# MMU8L.net
KiCad netlist of a schematic drawn in EAGLE
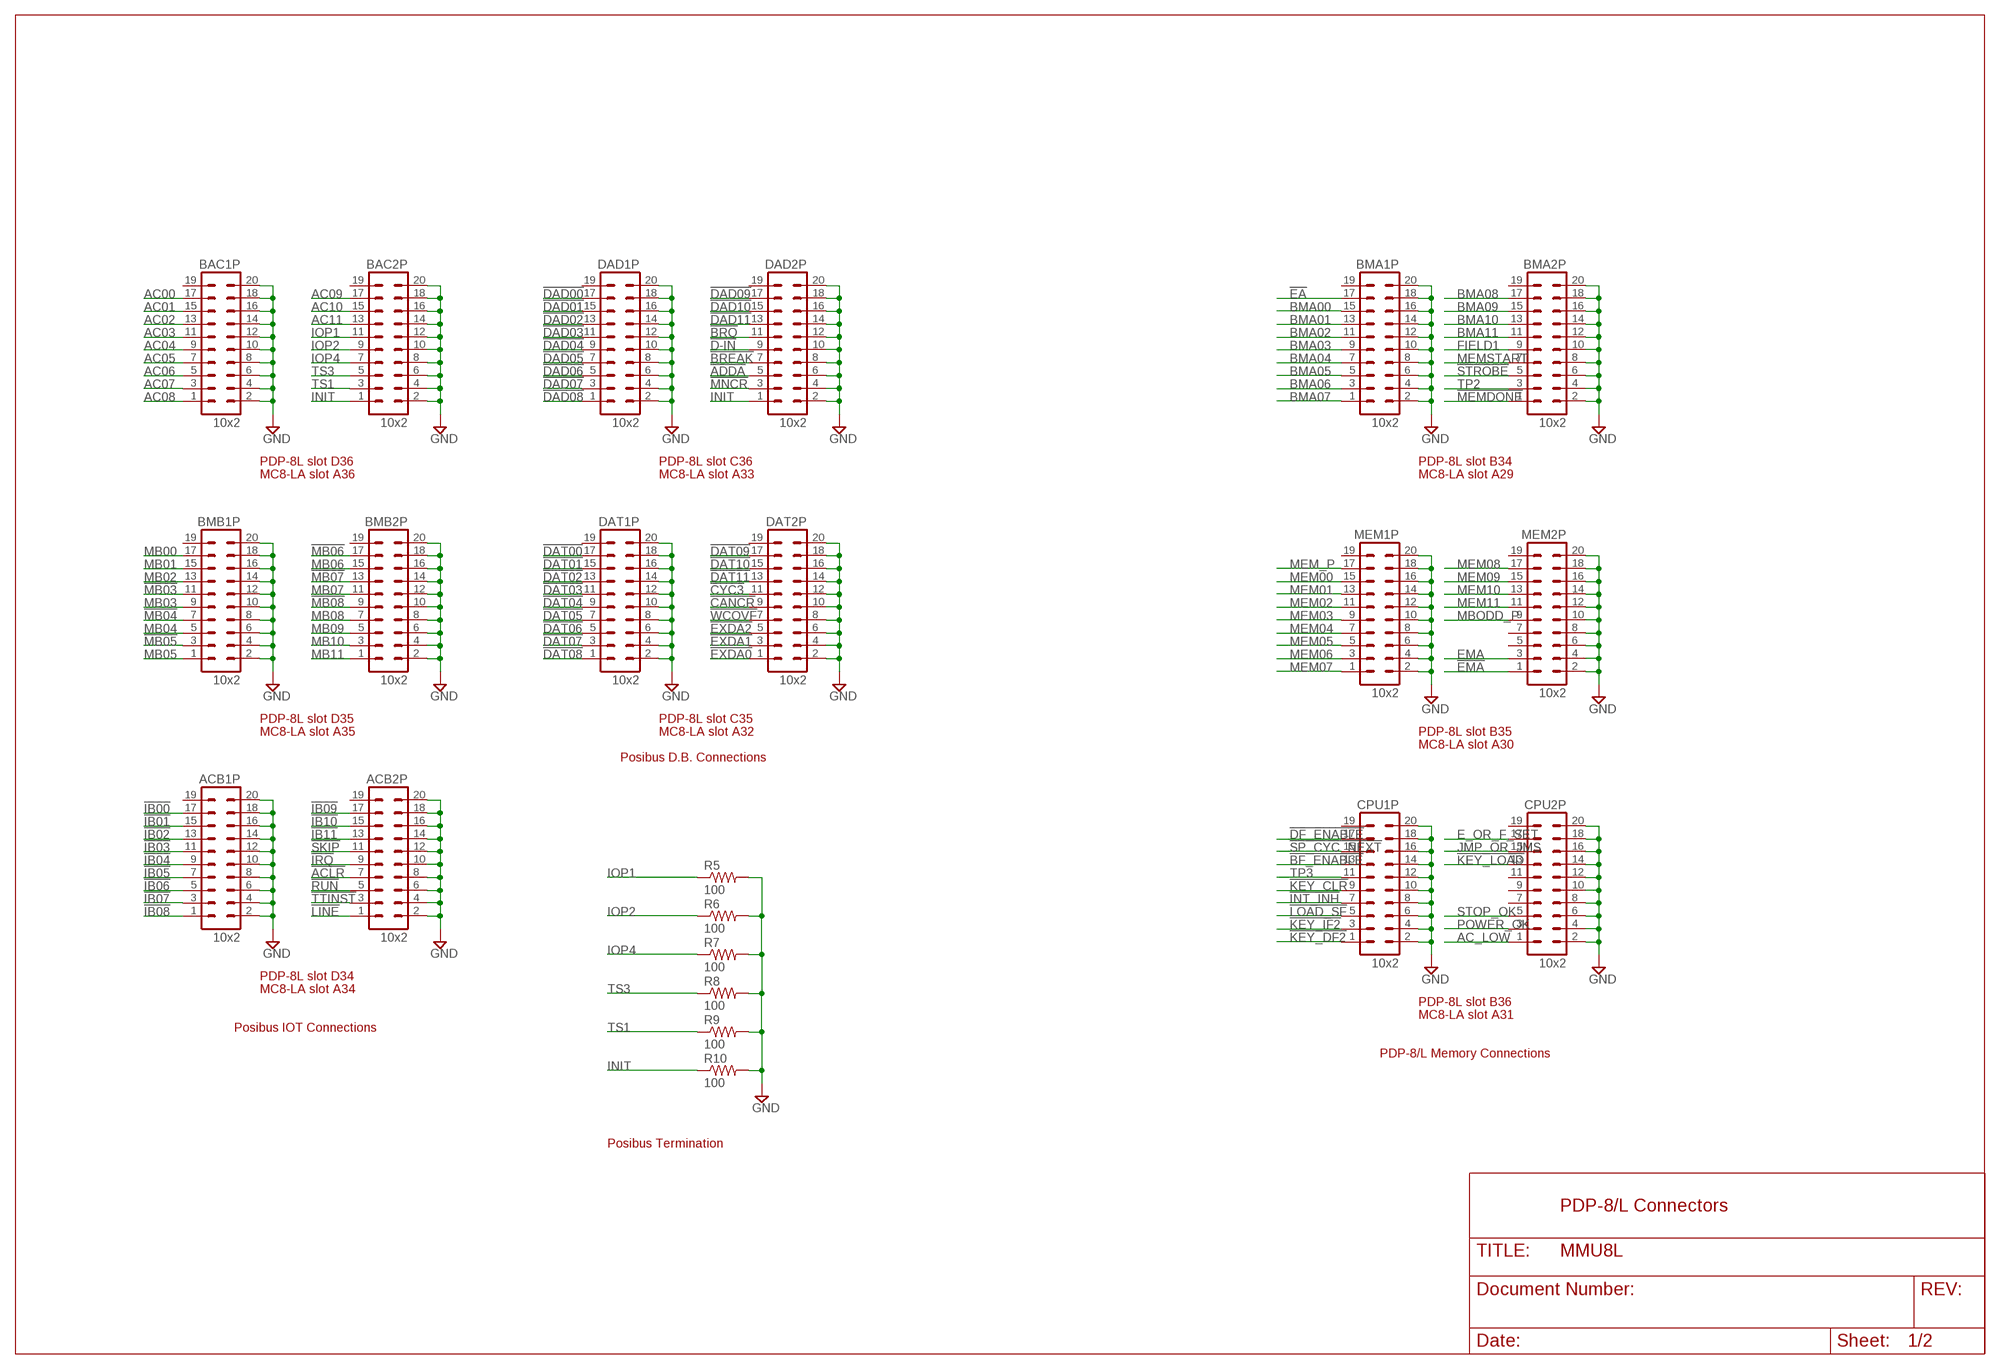
[diagram p0: schematic, sheet 1]
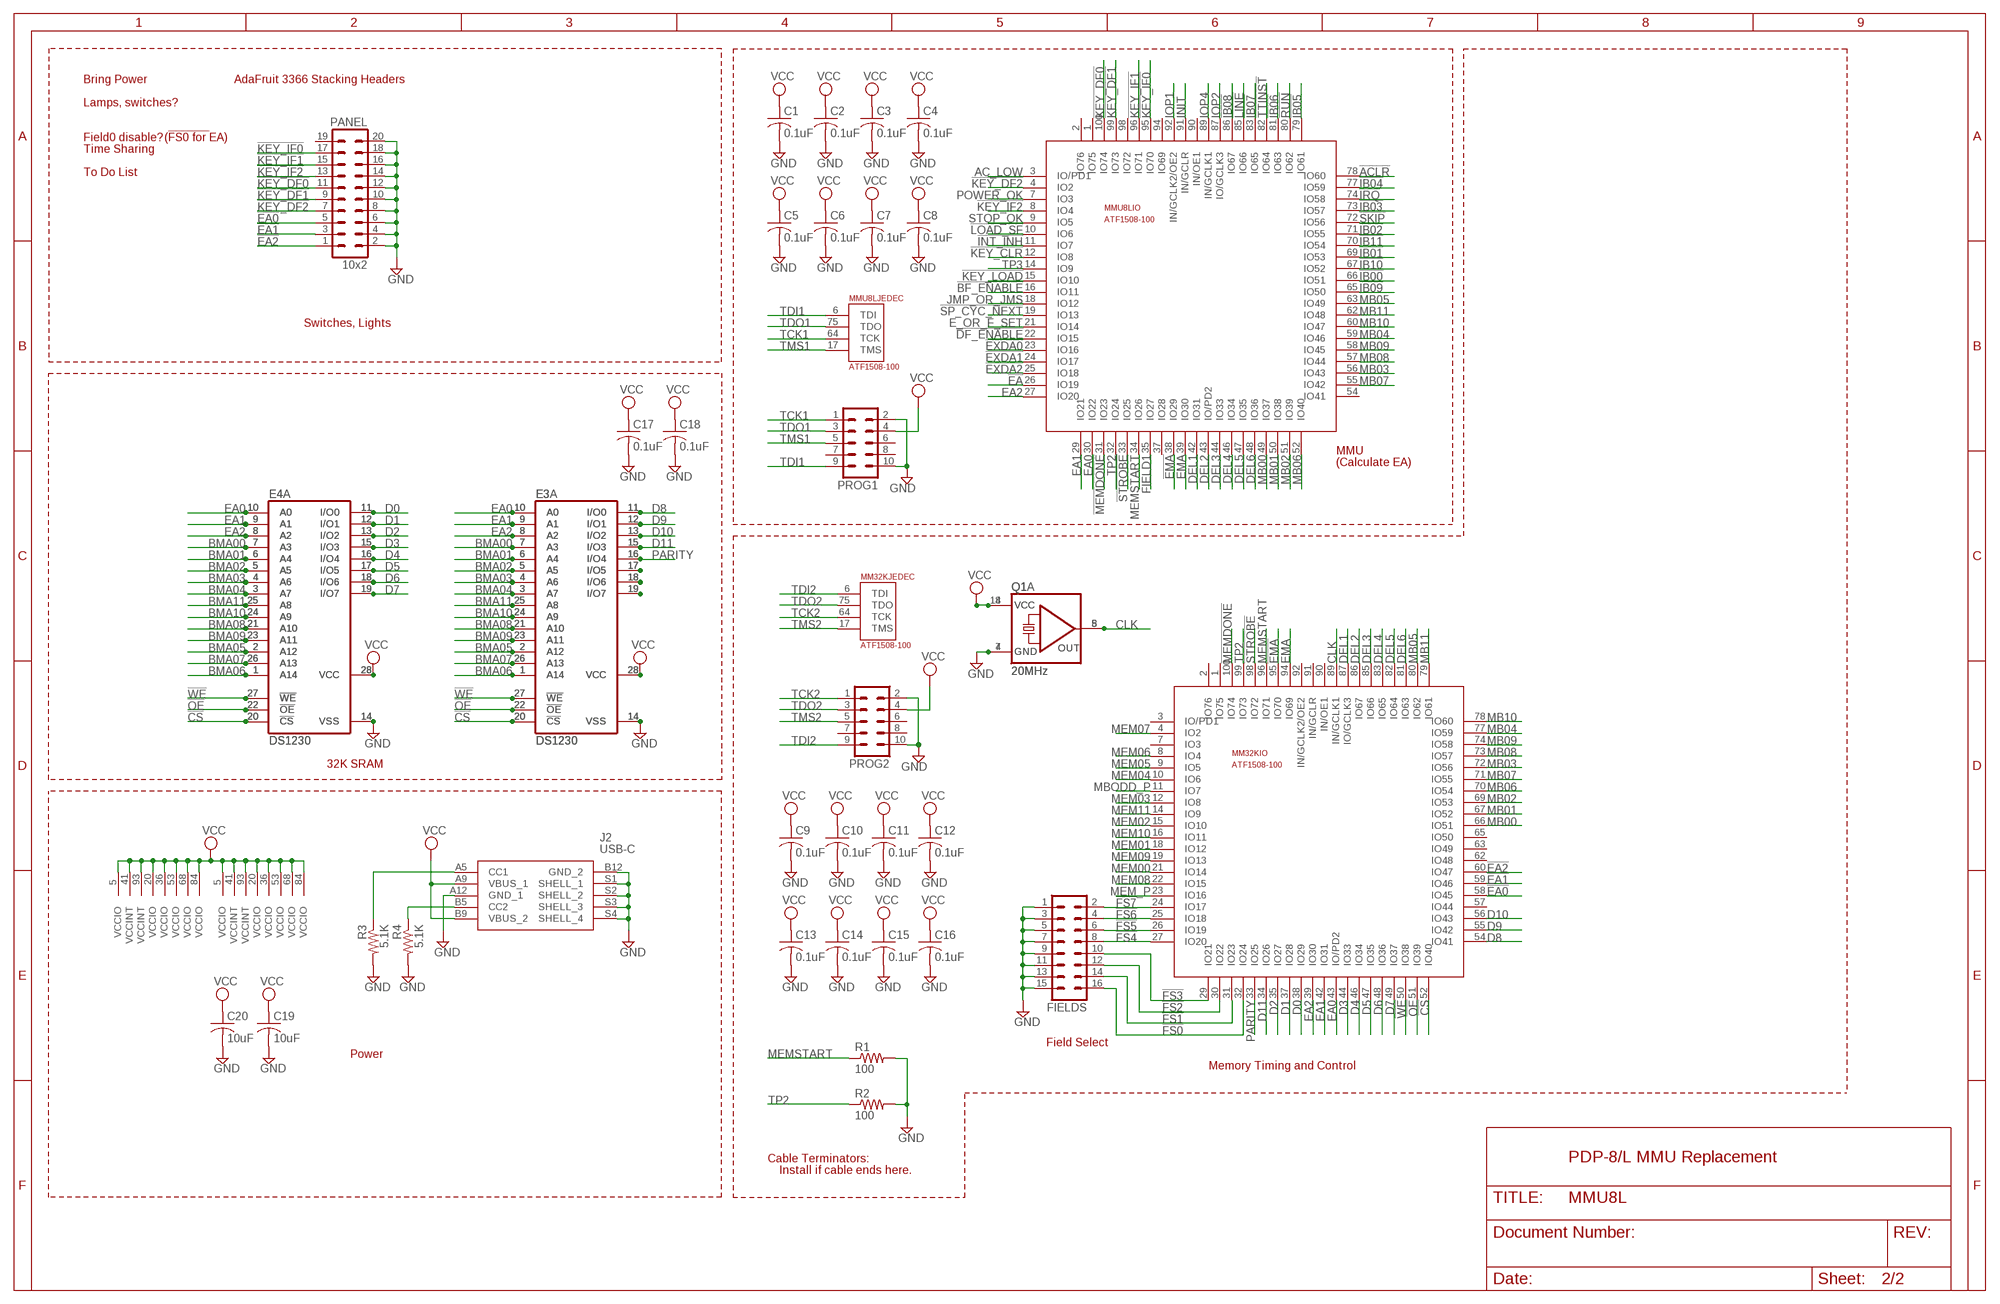
[diagram p1: schematic, sheet 2]

(export (version "E")
  (design (tool "Eeschema 10.0.6"))
  (components
    (comp (ref "C1")
      (value "0.1uF")
      (footprint "eagle-import:C0805")
      (libsource (lib "eagle-import") (part "C-USC0805"))
    )
    (comp (ref "C2")
      (value "0.1uF")
      (footprint "eagle-import:C0805")
      (libsource (lib "eagle-import") (part "C-USC0805"))
    )
    (comp (ref "C3")
      (value "0.1uF")
      (footprint "eagle-import:C0805")
      (libsource (lib "eagle-import") (part "C-USC0805"))
    )
    (comp (ref "C4")
      (value "0.1uF")
      (footprint "eagle-import:C0805")
      (libsource (lib "eagle-import") (part "C-USC0805"))
    )
    (comp (ref "C5")
      (value "0.1uF")
      (footprint "eagle-import:C0805")
      (libsource (lib "eagle-import") (part "C-USC0805"))
    )
    (comp (ref "C6")
      (value "0.1uF")
      (footprint "eagle-import:C0805")
      (libsource (lib "eagle-import") (part "C-USC0805"))
    )
    (comp (ref "C7")
      (value "0.1uF")
      (footprint "eagle-import:C0805")
      (libsource (lib "eagle-import") (part "C-USC0805"))
    )
    (comp (ref "C8")
      (value "0.1uF")
      (footprint "eagle-import:C0805")
      (libsource (lib "eagle-import") (part "C-USC0805"))
    )
    (comp (ref "C9")
      (value "0.1uF")
      (footprint "eagle-import:C0805")
      (libsource (lib "eagle-import") (part "C-USC0805"))
    )
    (comp (ref "C10")
      (value "0.1uF")
      (footprint "eagle-import:C0805")
      (libsource (lib "eagle-import") (part "C-USC0805"))
    )
    (comp (ref "C11")
      (value "0.1uF")
      (footprint "eagle-import:C0805")
      (libsource (lib "eagle-import") (part "C-USC0805"))
    )
    (comp (ref "C12")
      (value "0.1uF")
      (footprint "eagle-import:C0805")
      (libsource (lib "eagle-import") (part "C-USC0805"))
    )
    (comp (ref "C13")
      (value "0.1uF")
      (footprint "eagle-import:C0805")
      (libsource (lib "eagle-import") (part "C-USC0805"))
    )
    (comp (ref "C14")
      (value "0.1uF")
      (footprint "eagle-import:C0805")
      (libsource (lib "eagle-import") (part "C-USC0805"))
    )
    (comp (ref "C15")
      (value "0.1uF")
      (footprint "eagle-import:C0805")
      (libsource (lib "eagle-import") (part "C-USC0805"))
    )
    (comp (ref "C16")
      (value "0.1uF")
      (footprint "eagle-import:C0805")
      (libsource (lib "eagle-import") (part "C-USC0805"))
    )
    (comp (ref "C17")
      (value "0.1uF")
      (footprint "eagle-import:C0805")
      (libsource (lib "eagle-import") (part "C-USC0805"))
    )
    (comp (ref "C18")
      (value "0.1uF")
      (footprint "eagle-import:C0805")
      (libsource (lib "eagle-import") (part "C-USC0805"))
    )
    (comp (ref "C19")
      (value "10uF")
      (footprint "eagle-import:C0805")
      (libsource (lib "eagle-import") (part "C-USC0805"))
    )
    (comp (ref "C20")
      (value "10uF")
      (footprint "eagle-import:C0805")
      (libsource (lib "eagle-import") (part "C-USC0805"))
    )
    (comp (ref "E3")
      (value "DS1230")
      (footprint "eagle-import:DIL28-6")
      (libsource (lib "eagle-import") (part "62256P"))
    )
    (comp (ref "E3A")
      (value "DS1230")
      (footprint "eagle-import:DIL28-3")
      (libsource (lib "eagle-import") (part "62832P"))
    )
    (comp (ref "E4")
      (value "DS1230")
      (footprint "eagle-import:DIL28-6")
      (libsource (lib "eagle-import") (part "62256P"))
    )
    (comp (ref "E4A")
      (value "DS1230")
      (footprint "eagle-import:DIL28-3")
      (libsource (lib "eagle-import") (part "62832P"))
    )
    (comp (ref "FIELDS")
      (value "MA08-2")
      (footprint "eagle-import:MA08-2")
      (libsource (lib "eagle-import") (part "MA08-2"))
    )
    (comp (ref "J2")
      (value "USB-C")
      (footprint "eagle-import:USB497000A")
      (fields (field (name "MANUFACTURER_PART_NUMBER") "USB4970-00-A"))
      (libsource (lib "eagle-import") (part "USB4970-00-A"))
    )
    (comp (ref "MM32K")
      (value "ATF1508-100")
      (footprint "eagle-import:PQFP-100")
      (libsource (lib "eagle-import") (part "ATF150X100PQFP"))
    )
    (comp (ref "MMU8L")
      (value "ATF1508-100")
      (footprint "eagle-import:PQFP-100")
      (libsource (lib "eagle-import") (part "ATF150X100PQFP"))
    )
    (comp (ref "PANEL")
      (value "10x2")
      (footprint "eagle-import:MA10-2")
      (libsource (lib "eagle-import") (part "MA10-2"))
    )
    (comp (ref "PROG1")
      (value "ML10")
      (footprint "eagle-import:ML10")
      (libsource (lib "eagle-import") (part "ML10"))
    )
    (comp (ref "PROG2")
      (value "ML10")
      (footprint "eagle-import:ML10")
      (libsource (lib "eagle-import") (part "ML10"))
    )
    (comp (ref "Q1")
      (value "20MHz")
      (footprint "eagle-import:DIL14S")
      (libsource (lib "eagle-import") (part "QG5860"))
    )
    (comp (ref "Q1A")
      (value "20MHz")
      (footprint "eagle-import:DIL08S")
      (libsource (lib "eagle-import") (part "QG5460"))
    )
    (comp (ref "R1")
      (value "100")
      (footprint "eagle-import:R1206")
      (libsource (lib "eagle-import") (part "R-US_R1206"))
    )
    (comp (ref "R2")
      (value "100")
      (footprint "eagle-import:R1206")
      (libsource (lib "eagle-import") (part "R-US_R1206"))
    )
    (comp (ref "R3")
      (value "5.1K")
      (footprint "eagle-import:R0805")
      (libsource (lib "eagle-import") (part "R-US_R0805"))
    )
    (comp (ref "R4")
      (value "5.1K")
      (footprint "eagle-import:R0805")
      (libsource (lib "eagle-import") (part "R-US_R0805"))
    )
    (comp (ref "ACB1P")
      (value "10x2")
      (footprint "eagle-import:MA10-2")
      (libsource (lib "eagle-import") (part "MA10-2"))
    )
    (comp (ref "ACB2P")
      (value "10x2")
      (footprint "eagle-import:MA10-2")
      (libsource (lib "eagle-import") (part "MA10-2"))
    )
    (comp (ref "BAC1P")
      (value "10x2")
      (footprint "eagle-import:MA10-2")
      (libsource (lib "eagle-import") (part "MA10-2"))
    )
    (comp (ref "BAC2P")
      (value "10x2")
      (footprint "eagle-import:MA10-2")
      (libsource (lib "eagle-import") (part "MA10-2"))
    )
    (comp (ref "BMA1P")
      (value "10x2")
      (footprint "eagle-import:MA10-2")
      (libsource (lib "eagle-import") (part "MA10-2"))
    )
    (comp (ref "BMA2P")
      (value "10x2")
      (footprint "eagle-import:MA10-2")
      (libsource (lib "eagle-import") (part "MA10-2"))
    )
    (comp (ref "BMB1P")
      (value "10x2")
      (footprint "eagle-import:MA10-2")
      (libsource (lib "eagle-import") (part "MA10-2"))
    )
    (comp (ref "BMB2P")
      (value "10x2")
      (footprint "eagle-import:MA10-2")
      (libsource (lib "eagle-import") (part "MA10-2"))
    )
    (comp (ref "CPU1P")
      (value "10x2")
      (footprint "eagle-import:MA10-2")
      (libsource (lib "eagle-import") (part "MA10-2"))
    )
    (comp (ref "CPU2P")
      (value "10x2")
      (footprint "eagle-import:MA10-2")
      (libsource (lib "eagle-import") (part "MA10-2"))
    )
    (comp (ref "DAD1P")
      (value "10x2")
      (footprint "eagle-import:MA10-2")
      (libsource (lib "eagle-import") (part "MA10-2"))
    )
    (comp (ref "DAD2P")
      (value "10x2")
      (footprint "eagle-import:MA10-2")
      (libsource (lib "eagle-import") (part "MA10-2"))
    )
    (comp (ref "DAT1P")
      (value "10x2")
      (footprint "eagle-import:MA10-2")
      (libsource (lib "eagle-import") (part "MA10-2"))
    )
    (comp (ref "DAT2P")
      (value "10x2")
      (footprint "eagle-import:MA10-2")
      (libsource (lib "eagle-import") (part "MA10-2"))
    )
    (comp (ref "MEM1P")
      (value "10x2")
      (footprint "eagle-import:MA10-2")
      (libsource (lib "eagle-import") (part "MA10-2"))
    )
    (comp (ref "MEM2P")
      (value "10x2")
      (footprint "eagle-import:MA10-2")
      (libsource (lib "eagle-import") (part "MA10-2"))
    )
    (comp (ref "R5")
      (value "100")
      (footprint "eagle-import:R1206")
      (libsource (lib "eagle-import") (part "R-US_R1206"))
    )
    (comp (ref "R6")
      (value "100")
      (footprint "eagle-import:R1206")
      (libsource (lib "eagle-import") (part "R-US_R1206"))
    )
    (comp (ref "R7")
      (value "100")
      (footprint "eagle-import:R1206")
      (libsource (lib "eagle-import") (part "R-US_R1206"))
    )
    (comp (ref "R8")
      (value "100")
      (footprint "eagle-import:R1206")
      (libsource (lib "eagle-import") (part "R-US_R1206"))
    )
    (comp (ref "R9")
      (value "100")
      (footprint "eagle-import:R1206")
      (libsource (lib "eagle-import") (part "R-US_R1206"))
    )
    (comp (ref "R10")
      (value "100")
      (footprint "eagle-import:R1206")
      (libsource (lib "eagle-import") (part "R-US_R1206"))
    )
  )
  (nets
    (net (code "1") (name "AC00") (class "Default")
      (node (ref "BAC1P") (pin "17") (pinfunction "17_17") (pintype "passive"))
    )
    (net (code "2") (name "AC01") (class "Default")
      (node (ref "BAC1P") (pin "15") (pinfunction "15_15") (pintype "passive"))
    )
    (net (code "3") (name "AC02") (class "Default")
      (node (ref "BAC1P") (pin "13") (pinfunction "13_13") (pintype "passive"))
    )
    (net (code "4") (name "AC03") (class "Default")
      (node (ref "BAC1P") (pin "11") (pinfunction "11_11") (pintype "passive"))
    )
    (net (code "5") (name "AC04") (class "Default")
      (node (ref "BAC1P") (pin "9") (pinfunction "9_9") (pintype "passive"))
    )
    (net (code "6") (name "AC05") (class "Default")
      (node (ref "BAC1P") (pin "7") (pinfunction "7_7") (pintype "passive"))
    )
    (net (code "7") (name "AC06") (class "Default")
      (node (ref "BAC1P") (pin "5") (pinfunction "5_5") (pintype "passive"))
    )
    (net (code "8") (name "AC07") (class "Default")
      (node (ref "BAC1P") (pin "3") (pinfunction "3_3") (pintype "passive"))
    )
    (net (code "9") (name "AC08") (class "Default")
      (node (ref "BAC1P") (pin "1") (pinfunction "1_1") (pintype "passive"))
    )
    (net (code "10") (name "AC09") (class "Default")
      (node (ref "BAC2P") (pin "17") (pinfunction "17_17") (pintype "passive"))
    )
    (net (code "11") (name "AC10") (class "Default")
      (node (ref "BAC2P") (pin "15") (pinfunction "15_15") (pintype "passive"))
    )
    (net (code "12") (name "AC11") (class "Default")
      (node (ref "BAC2P") (pin "13") (pinfunction "13_13") (pintype "passive"))
    )
    (net (code "13") (name "AC_LOW") (class "Default")
      (node (ref "CPU2P") (pin "1") (pinfunction "1_1") (pintype "passive"))
      (node (ref "MMU8L") (pin "3") (pinfunction "IO/PD1_3") (pintype "bidirectional"))
    )
    (net (code "14") (name "BMA00") (class "Default")
      (node (ref "BMA1P") (pin "15") (pinfunction "15_15") (pintype "passive"))
      (node (ref "E3") (pin "7") (pinfunction "A3_7") (pintype "input"))
      (node (ref "E3A") (pin "7") (pinfunction "A3_7") (pintype "input"))
      (node (ref "E4") (pin "7") (pinfunction "A3_7") (pintype "input"))
      (node (ref "E4A") (pin "7") (pinfunction "A3_7") (pintype "input"))
    )
    (net (code "15") (name "BMA01") (class "Default")
      (node (ref "BMA1P") (pin "13") (pinfunction "13_13") (pintype "passive"))
      (node (ref "E3") (pin "6") (pinfunction "A4_6") (pintype "input"))
      (node (ref "E3A") (pin "6") (pinfunction "A4_6") (pintype "input"))
      (node (ref "E4") (pin "6") (pinfunction "A4_6") (pintype "input"))
      (node (ref "E4A") (pin "6") (pinfunction "A4_6") (pintype "input"))
    )
    (net (code "16") (name "BMA02") (class "Default")
      (node (ref "BMA1P") (pin "11") (pinfunction "11_11") (pintype "passive"))
      (node (ref "E3") (pin "5") (pinfunction "A5_5") (pintype "input"))
      (node (ref "E3A") (pin "5") (pinfunction "A5_5") (pintype "input"))
      (node (ref "E4") (pin "5") (pinfunction "A5_5") (pintype "input"))
      (node (ref "E4A") (pin "5") (pinfunction "A5_5") (pintype "input"))
    )
    (net (code "17") (name "BMA03") (class "Default")
      (node (ref "BMA1P") (pin "9") (pinfunction "9_9") (pintype "passive"))
      (node (ref "E3") (pin "4") (pinfunction "A6_4") (pintype "input"))
      (node (ref "E3A") (pin "4") (pinfunction "A6_4") (pintype "input"))
      (node (ref "E4") (pin "4") (pinfunction "A6_4") (pintype "input"))
      (node (ref "E4A") (pin "4") (pinfunction "A6_4") (pintype "input"))
    )
    (net (code "18") (name "BMA04") (class "Default")
      (node (ref "BMA1P") (pin "7") (pinfunction "7_7") (pintype "passive"))
      (node (ref "E3") (pin "3") (pinfunction "A7_3") (pintype "input"))
      (node (ref "E3A") (pin "3") (pinfunction "A7_3") (pintype "input"))
      (node (ref "E4") (pin "3") (pinfunction "A7_3") (pintype "input"))
      (node (ref "E4A") (pin "3") (pinfunction "A7_3") (pintype "input"))
    )
    (net (code "19") (name "BMA05") (class "Default")
      (node (ref "BMA1P") (pin "5") (pinfunction "5_5") (pintype "passive"))
      (node (ref "E3") (pin "2") (pinfunction "A12_2") (pintype "input"))
      (node (ref "E3A") (pin "2") (pinfunction "A12_2") (pintype "input"))
      (node (ref "E4") (pin "2") (pinfunction "A12_2") (pintype "input"))
      (node (ref "E4A") (pin "2") (pinfunction "A12_2") (pintype "input"))
    )
    (net (code "20") (name "BMA06") (class "Default")
      (node (ref "BMA1P") (pin "3") (pinfunction "3_3") (pintype "passive"))
      (node (ref "E3") (pin "1") (pinfunction "A14_1") (pintype "input"))
      (node (ref "E3A") (pin "1") (pinfunction "A14_1") (pintype "input"))
      (node (ref "E4") (pin "1") (pinfunction "A14_1") (pintype "input"))
      (node (ref "E4A") (pin "1") (pinfunction "A14_1") (pintype "input"))
    )
    (net (code "21") (name "BMA07") (class "Default")
      (node (ref "BMA1P") (pin "1") (pinfunction "1_1") (pintype "passive"))
      (node (ref "E3") (pin "26") (pinfunction "A13_26") (pintype "input"))
      (node (ref "E3A") (pin "26") (pinfunction "A13_26") (pintype "input"))
      (node (ref "E4") (pin "26") (pinfunction "A13_26") (pintype "input"))
      (node (ref "E4A") (pin "26") (pinfunction "A13_26") (pintype "input"))
    )
    (net (code "22") (name "BMA08") (class "Default")
      (node (ref "BMA2P") (pin "17") (pinfunction "17_17") (pintype "passive"))
      (node (ref "E3") (pin "21") (pinfunction "A10_21") (pintype "input"))
      (node (ref "E3A") (pin "21") (pinfunction "A10_21") (pintype "input"))
      (node (ref "E4") (pin "21") (pinfunction "A10_21") (pintype "input"))
      (node (ref "E4A") (pin "21") (pinfunction "A10_21") (pintype "input"))
    )
    (net (code "23") (name "BMA09") (class "Default")
      (node (ref "BMA2P") (pin "15") (pinfunction "15_15") (pintype "passive"))
      (node (ref "E3") (pin "23") (pinfunction "A11_23") (pintype "input"))
      (node (ref "E3A") (pin "23") (pinfunction "A11_23") (pintype "input"))
      (node (ref "E4") (pin "23") (pinfunction "A11_23") (pintype "input"))
      (node (ref "E4A") (pin "23") (pinfunction "A11_23") (pintype "input"))
    )
    (net (code "24") (name "BMA10") (class "Default")
      (node (ref "BMA2P") (pin "13") (pinfunction "13_13") (pintype "passive"))
      (node (ref "E3") (pin "24") (pinfunction "A9_24") (pintype "input"))
      (node (ref "E3A") (pin "24") (pinfunction "A9_24") (pintype "input"))
      (node (ref "E4") (pin "24") (pinfunction "A9_24") (pintype "input"))
      (node (ref "E4A") (pin "24") (pinfunction "A9_24") (pintype "input"))
    )
    (net (code "25") (name "BMA11") (class "Default")
      (node (ref "BMA2P") (pin "11") (pinfunction "11_11") (pintype "passive"))
      (node (ref "E3") (pin "25") (pinfunction "A8_25") (pintype "input"))
      (node (ref "E3A") (pin "25") (pinfunction "A8_25") (pintype "input"))
      (node (ref "E4") (pin "25") (pinfunction "A8_25") (pintype "input"))
      (node (ref "E4A") (pin "25") (pinfunction "A8_25") (pintype "input"))
    )
    (net (code "26") (name "CLK") (class "Default")
      (node (ref "MM32K") (pin "89") (pinfunction "IN/GCLK1_89") (pintype "input"))
      (node (ref "Q1") (pin "8") (pinfunction "OUT_8") (pintype "output"))
      (node (ref "Q1A") (pin "5") (pinfunction "OUT_5") (pintype "output"))
    )
    (net (code "27") (name "D0") (class "Default")
      (node (ref "E4") (pin "11") (pinfunction "I/O0_11") (pintype "bidirectional"))
      (node (ref "E4A") (pin "11") (pinfunction "I/O0_11") (pintype "bidirectional"))
      (node (ref "MM32K") (pin "38") (pinfunction "IO29_38") (pintype "bidirectional"))
    )
    (net (code "28") (name "D1") (class "Default")
      (node (ref "E4") (pin "12") (pinfunction "I/O1_12") (pintype "bidirectional"))
      (node (ref "E4A") (pin "12") (pinfunction "I/O1_12") (pintype "bidirectional"))
      (node (ref "MM32K") (pin "37") (pinfunction "IO28_37") (pintype "bidirectional"))
    )
    (net (code "29") (name "D2") (class "Default")
      (node (ref "E4") (pin "13") (pinfunction "I/O2_13") (pintype "bidirectional"))
      (node (ref "E4A") (pin "13") (pinfunction "I/O2_13") (pintype "bidirectional"))
      (node (ref "MM32K") (pin "35") (pinfunction "IO27_35") (pintype "bidirectional"))
    )
    (net (code "30") (name "D3") (class "Default")
      (node (ref "E4") (pin "15") (pinfunction "I/O3_15") (pintype "bidirectional"))
      (node (ref "E4A") (pin "15") (pinfunction "I/O3_15") (pintype "bidirectional"))
      (node (ref "MM32K") (pin "44") (pinfunction "IO33_44") (pintype "bidirectional"))
    )
    (net (code "31") (name "D4") (class "Default")
      (node (ref "E4") (pin "16") (pinfunction "I/O4_16") (pintype "bidirectional"))
      (node (ref "E4A") (pin "16") (pinfunction "I/O4_16") (pintype "bidirectional"))
      (node (ref "MM32K") (pin "46") (pinfunction "IO34_46") (pintype "bidirectional"))
    )
    (net (code "32") (name "D5") (class "Default")
      (node (ref "E4") (pin "17") (pinfunction "I/O5_17") (pintype "bidirectional"))
      (node (ref "E4A") (pin "17") (pinfunction "I/O5_17") (pintype "bidirectional"))
      (node (ref "MM32K") (pin "47") (pinfunction "IO35_47") (pintype "bidirectional"))
    )
    (net (code "33") (name "D6") (class "Default")
      (node (ref "E4") (pin "18") (pinfunction "I/O6_18") (pintype "bidirectional"))
      (node (ref "E4A") (pin "18") (pinfunction "I/O6_18") (pintype "bidirectional"))
      (node (ref "MM32K") (pin "48") (pinfunction "IO36_48") (pintype "bidirectional"))
    )
    (net (code "34") (name "D7") (class "Default")
      (node (ref "E4") (pin "19") (pinfunction "I/O7_19") (pintype "bidirectional"))
      (node (ref "E4A") (pin "19") (pinfunction "I/O7_19") (pintype "bidirectional"))
      (node (ref "MM32K") (pin "49") (pinfunction "IO37_49") (pintype "bidirectional"))
    )
    (net (code "35") (name "D8") (class "Default")
      (node (ref "E3") (pin "11") (pinfunction "I/O0_11") (pintype "bidirectional"))
      (node (ref "E3A") (pin "11") (pinfunction "I/O0_11") (pintype "bidirectional"))
      (node (ref "MM32K") (pin "54") (pinfunction "IO41_54") (pintype "bidirectional"))
    )
    (net (code "36") (name "D9") (class "Default")
      (node (ref "E3") (pin "12") (pinfunction "I/O1_12") (pintype "bidirectional"))
      (node (ref "E3A") (pin "12") (pinfunction "I/O1_12") (pintype "bidirectional"))
      (node (ref "MM32K") (pin "55") (pinfunction "IO42_55") (pintype "bidirectional"))
    )
    (net (code "37") (name "D10") (class "Default")
      (node (ref "E3") (pin "13") (pinfunction "I/O2_13") (pintype "bidirectional"))
      (node (ref "E3A") (pin "13") (pinfunction "I/O2_13") (pintype "bidirectional"))
      (node (ref "MM32K") (pin "56") (pinfunction "IO43_56") (pintype "bidirectional"))
    )
    (net (code "38") (name "D11") (class "Default")
      (node (ref "E3") (pin "15") (pinfunction "I/O3_15") (pintype "bidirectional"))
      (node (ref "E3A") (pin "15") (pinfunction "I/O3_15") (pintype "bidirectional"))
      (node (ref "MM32K") (pin "34") (pinfunction "IO26_34") (pintype "bidirectional"))
    )
    (net (code "39") (name "DEL1") (class "Default")
      (node (ref "MM32K") (pin "87") (pinfunction "IO/GCLK3_87") (pintype "bidirectional"))
      (node (ref "MMU8L") (pin "42") (pinfunction "IO31_42") (pintype "bidirectional"))
    )
    (net (code "40") (name "DEL2") (class "Default")
      (node (ref "MM32K") (pin "86") (pinfunction "IO67_86") (pintype "bidirectional"))
      (node (ref "MMU8L") (pin "43") (pinfunction "IO/PD2_43") (pintype "bidirectional"))
    )
    (net (code "41") (name "DEL3") (class "Default")
      (node (ref "MM32K") (pin "85") (pinfunction "IO66_85") (pintype "bidirectional"))
      (node (ref "MMU8L") (pin "44") (pinfunction "IO33_44") (pintype "bidirectional"))
    )
    (net (code "42") (name "DEL4") (class "Default")
      (node (ref "MM32K") (pin "83") (pinfunction "IO65_83") (pintype "bidirectional"))
      (node (ref "MMU8L") (pin "46") (pinfunction "IO34_46") (pintype "bidirectional"))
    )
    (net (code "43") (name "DEL5") (class "Default")
      (node (ref "MM32K") (pin "82") (pinfunction "IO64_82") (pintype "bidirectional"))
      (node (ref "MMU8L") (pin "47") (pinfunction "IO35_47") (pintype "bidirectional"))
    )
    (net (code "44") (name "DEL6") (class "Default")
      (node (ref "MM32K") (pin "81") (pinfunction "IO63_81") (pintype "bidirectional"))
      (node (ref "MMU8L") (pin "48") (pinfunction "IO36_48") (pintype "bidirectional"))
    )
    (net (code "45") (name "EA0") (class "Default")
      (node (ref "E3") (pin "10") (pinfunction "A0_10") (pintype "input"))
      (node (ref "E3A") (pin "10") (pinfunction "A0_10") (pintype "input"))
      (node (ref "E4") (pin "10") (pinfunction "A0_10") (pintype "input"))
      (node (ref "E4A") (pin "10") (pinfunction "A0_10") (pintype "input"))
      (node (ref "MM32K") (pin "43") (pinfunction "IO/PD2_43") (pintype "bidirectional"))
      (node (ref "MMU8L") (pin "30") (pinfunction "IO22_30") (pintype "bidirectional"))
    )
    (net (code "46") (name "EA1") (class "Default")
      (node (ref "E3") (pin "9") (pinfunction "A1_9") (pintype "input"))
      (node (ref "E3A") (pin "9") (pinfunction "A1_9") (pintype "input"))
      (node (ref "E4") (pin "9") (pinfunction "A1_9") (pintype "input"))
      (node (ref "E4A") (pin "9") (pinfunction "A1_9") (pintype "input"))
      (node (ref "MM32K") (pin "42") (pinfunction "IO31_42") (pintype "bidirectional"))
      (node (ref "MMU8L") (pin "29") (pinfunction "IO21_29") (pintype "bidirectional"))
    )
    (net (code "47") (name "EA2") (class "Default")
      (node (ref "E3") (pin "8") (pinfunction "A2_8") (pintype "input"))
      (node (ref "E3A") (pin "8") (pinfunction "A2_8") (pintype "input"))
      (node (ref "E4") (pin "8") (pinfunction "A2_8") (pintype "input"))
      (node (ref "E4A") (pin "8") (pinfunction "A2_8") (pintype "input"))
      (node (ref "MM32K") (pin "39") (pinfunction "IO30_39") (pintype "bidirectional"))
      (node (ref "MMU8L") (pin "27") (pinfunction "IO20_27") (pintype "bidirectional"))
    )
    (net (code "48") (name "EMA") (class "Default")
      (node (ref "MEM2P") (pin "3") (pinfunction "3_3") (pintype "passive"))
      (node (ref "MM32K") (pin "94") (pinfunction "IO69_94") (pintype "bidirectional"))
      (node (ref "MMU8L") (pin "39") (pinfunction "IO30_39") (pintype "bidirectional"))
    )
    (net (code "49") (name "E_OR_F_SET") (class "Default")
      (node (ref "CPU2P") (pin "17") (pinfunction "17_17") (pintype "passive"))
      (node (ref "MMU8L") (pin "21") (pinfunction "IO14_21") (pintype "bidirectional"))
    )
    (net (code "50") (name "FIELD1") (class "Default")
      (node (ref "BMA2P") (pin "9") (pinfunction "9_9") (pintype "passive"))
      (node (ref "MMU8L") (pin "35") (pinfunction "IO27_35") (pintype "bidirectional"))
    )
    (net (code "51") (name "GND") (class "Default")
      (node (ref "ACB1P") (pin "10") (pinfunction "10_10") (pintype "passive"))
      (node (ref "ACB1P") (pin "12") (pinfunction "12_12") (pintype "passive"))
      (node (ref "ACB1P") (pin "14") (pinfunction "14_14") (pintype "passive"))
      (node (ref "ACB1P") (pin "16") (pinfunction "16_16") (pintype "passive"))
      (node (ref "ACB1P") (pin "18") (pinfunction "18_18") (pintype "passive"))
      (node (ref "ACB1P") (pin "2") (pinfunction "2_2") (pintype "passive"))
      (node (ref "ACB1P") (pin "20") (pinfunction "20_20") (pintype "passive"))
      (node (ref "ACB1P") (pin "4") (pinfunction "4_4") (pintype "passive"))
      (node (ref "ACB1P") (pin "6") (pinfunction "6_6") (pintype "passive"))
      (node (ref "ACB1P") (pin "8") (pinfunction "8_8") (pintype "passive"))
      (node (ref "ACB2P") (pin "10") (pinfunction "10_10") (pintype "passive"))
      (node (ref "ACB2P") (pin "12") (pinfunction "12_12") (pintype "passive"))
      (node (ref "ACB2P") (pin "14") (pinfunction "14_14") (pintype "passive"))
      (node (ref "ACB2P") (pin "16") (pinfunction "16_16") (pintype "passive"))
      (node (ref "ACB2P") (pin "18") (pinfunction "18_18") (pintype "passive"))
      (node (ref "ACB2P") (pin "2") (pinfunction "2_2") (pintype "passive"))
      (node (ref "ACB2P") (pin "20") (pinfunction "20_20") (pintype "passive"))
      (node (ref "ACB2P") (pin "4") (pinfunction "4_4") (pintype "passive"))
      (node (ref "ACB2P") (pin "6") (pinfunction "6_6") (pintype "passive"))
      (node (ref "ACB2P") (pin "8") (pinfunction "8_8") (pintype "passive"))
      (node (ref "BAC1P") (pin "10") (pinfunction "10_10") (pintype "passive"))
      (node (ref "BAC1P") (pin "12") (pinfunction "12_12") (pintype "passive"))
      (node (ref "BAC1P") (pin "14") (pinfunction "14_14") (pintype "passive"))
      (node (ref "BAC1P") (pin "16") (pinfunction "16_16") (pintype "passive"))
      (node (ref "BAC1P") (pin "18") (pinfunction "18_18") (pintype "passive"))
      (node (ref "BAC1P") (pin "2") (pinfunction "2_2") (pintype "passive"))
      (node (ref "BAC1P") (pin "20") (pinfunction "20_20") (pintype "passive"))
      (node (ref "BAC1P") (pin "4") (pinfunction "4_4") (pintype "passive"))
      (node (ref "BAC1P") (pin "6") (pinfunction "6_6") (pintype "passive"))
      (node (ref "BAC1P") (pin "8") (pinfunction "8_8") (pintype "passive"))
      (node (ref "BAC2P") (pin "10") (pinfunction "10_10") (pintype "passive"))
      (node (ref "BAC2P") (pin "12") (pinfunction "12_12") (pintype "passive"))
      (node (ref "BAC2P") (pin "14") (pinfunction "14_14") (pintype "passive"))
      (node (ref "BAC2P") (pin "16") (pinfunction "16_16") (pintype "passive"))
      (node (ref "BAC2P") (pin "18") (pinfunction "18_18") (pintype "passive"))
      (node (ref "BAC2P") (pin "2") (pinfunction "2_2") (pintype "passive"))
      (node (ref "BAC2P") (pin "20") (pinfunction "20_20") (pintype "passive"))
      (node (ref "BAC2P") (pin "4") (pinfunction "4_4") (pintype "passive"))
      (node (ref "BAC2P") (pin "6") (pinfunction "6_6") (pintype "passive"))
      (node (ref "BAC2P") (pin "8") (pinfunction "8_8") (pintype "passive"))
      (node (ref "BMA1P") (pin "10") (pinfunction "10_10") (pintype "passive"))
      (node (ref "BMA1P") (pin "12") (pinfunction "12_12") (pintype "passive"))
      (node (ref "BMA1P") (pin "14") (pinfunction "14_14") (pintype "passive"))
      (node (ref "BMA1P") (pin "16") (pinfunction "16_16") (pintype "passive"))
      (node (ref "BMA1P") (pin "18") (pinfunction "18_18") (pintype "passive"))
      (node (ref "BMA1P") (pin "2") (pinfunction "2_2") (pintype "passive"))
      (node (ref "BMA1P") (pin "20") (pinfunction "20_20") (pintype "passive"))
      (node (ref "BMA1P") (pin "4") (pinfunction "4_4") (pintype "passive"))
      (node (ref "BMA1P") (pin "6") (pinfunction "6_6") (pintype "passive"))
      (node (ref "BMA1P") (pin "8") (pinfunction "8_8") (pintype "passive"))
      (node (ref "BMA2P") (pin "10") (pinfunction "10_10") (pintype "passive"))
      (node (ref "BMA2P") (pin "12") (pinfunction "12_12") (pintype "passive"))
      (node (ref "BMA2P") (pin "14") (pinfunction "14_14") (pintype "passive"))
      (node (ref "BMA2P") (pin "16") (pinfunction "16_16") (pintype "passive"))
      (node (ref "BMA2P") (pin "18") (pinfunction "18_18") (pintype "passive"))
      (node (ref "BMA2P") (pin "2") (pinfunction "2_2") (pintype "passive"))
      (node (ref "BMA2P") (pin "20") (pinfunction "20_20") (pintype "passive"))
      (node (ref "BMA2P") (pin "4") (pinfunction "4_4") (pintype "passive"))
      (node (ref "BMA2P") (pin "6") (pinfunction "6_6") (pintype "passive"))
      (node (ref "BMA2P") (pin "8") (pinfunction "8_8") (pintype "passive"))
      (node (ref "BMB1P") (pin "10") (pinfunction "10_10") (pintype "passive"))
      (node (ref "BMB1P") (pin "12") (pinfunction "12_12") (pintype "passive"))
      (node (ref "BMB1P") (pin "14") (pinfunction "14_14") (pintype "passive"))
      (node (ref "BMB1P") (pin "16") (pinfunction "16_16") (pintype "passive"))
      (node (ref "BMB1P") (pin "18") (pinfunction "18_18") (pintype "passive"))
      (node (ref "BMB1P") (pin "2") (pinfunction "2_2") (pintype "passive"))
      (node (ref "BMB1P") (pin "20") (pinfunction "20_20") (pintype "passive"))
      (node (ref "BMB1P") (pin "4") (pinfunction "4_4") (pintype "passive"))
      (node (ref "BMB1P") (pin "6") (pinfunction "6_6") (pintype "passive"))
      (node (ref "BMB1P") (pin "8") (pinfunction "8_8") (pintype "passive"))
      (node (ref "BMB2P") (pin "10") (pinfunction "10_10") (pintype "passive"))
      (node (ref "BMB2P") (pin "12") (pinfunction "12_12") (pintype "passive"))
      (node (ref "BMB2P") (pin "14") (pinfunction "14_14") (pintype "passive"))
      (node (ref "BMB2P") (pin "16") (pinfunction "16_16") (pintype "passive"))
      (node (ref "BMB2P") (pin "18") (pinfunction "18_18") (pintype "passive"))
      (node (ref "BMB2P") (pin "2") (pinfunction "2_2") (pintype "passive"))
      (node (ref "BMB2P") (pin "20") (pinfunction "20_20") (pintype "passive"))
      (node (ref "BMB2P") (pin "4") (pinfunction "4_4") (pintype "passive"))
      (node (ref "BMB2P") (pin "6") (pinfunction "6_6") (pintype "passive"))
      (node (ref "BMB2P") (pin "8") (pinfunction "8_8") (pintype "passive"))
      (node (ref "C1") (pin "2") (pinfunction "2_2") (pintype "passive"))
      (node (ref "C10") (pin "2") (pinfunction "2_2") (pintype "passive"))
      (node (ref "C11") (pin "2") (pinfunction "2_2") (pintype "passive"))
      (node (ref "C12") (pin "2") (pinfunction "2_2") (pintype "passive"))
      (node (ref "C13") (pin "2") (pinfunction "2_2") (pintype "passive"))
      (node (ref "C14") (pin "2") (pinfunction "2_2") (pintype "passive"))
      (node (ref "C15") (pin "2") (pinfunction "2_2") (pintype "passive"))
      (node (ref "C16") (pin "2") (pinfunction "2_2") (pintype "passive"))
      (node (ref "C17") (pin "2") (pinfunction "2_2") (pintype "passive"))
      (node (ref "C18") (pin "2") (pinfunction "2_2") (pintype "passive"))
      (node (ref "C19") (pin "2") (pinfunction "2_2") (pintype "passive"))
      (node (ref "C2") (pin "2") (pinfunction "2_2") (pintype "passive"))
      (node (ref "C20") (pin "2") (pinfunction "2_2") (pintype "passive"))
      (node (ref "C3") (pin "2") (pinfunction "2_2") (pintype "passive"))
      (node (ref "C4") (pin "2") (pinfunction "2_2") (pintype "passive"))
      (node (ref "C5") (pin "2") (pinfunction "2_2") (pintype "passive"))
      (node (ref "C6") (pin "2") (pinfunction "2_2") (pintype "passive"))
      (node (ref "C7") (pin "2") (pinfunction "2_2") (pintype "passive"))
      (node (ref "C8") (pin "2") (pinfunction "2_2") (pintype "passive"))
      (node (ref "C9") (pin "2") (pinfunction "2_2") (pintype "passive"))
      (node (ref "CPU1P") (pin "10") (pinfunction "10_10") (pintype "passive"))
      (node (ref "CPU1P") (pin "12") (pinfunction "12_12") (pintype "passive"))
      (node (ref "CPU1P") (pin "14") (pinfunction "14_14") (pintype "passive"))
      (node (ref "CPU1P") (pin "16") (pinfunction "16_16") (pintype "passive"))
      (node (ref "CPU1P") (pin "18") (pinfunction "18_18") (pintype "passive"))
      (node (ref "CPU1P") (pin "2") (pinfunction "2_2") (pintype "passive"))
      (node (ref "CPU1P") (pin "20") (pinfunction "20_20") (pintype "passive"))
      (node (ref "CPU1P") (pin "4") (pinfunction "4_4") (pintype "passive"))
      (node (ref "CPU1P") (pin "6") (pinfunction "6_6") (pintype "passive"))
      (node (ref "CPU1P") (pin "8") (pinfunction "8_8") (pintype "passive"))
      (node (ref "CPU2P") (pin "10") (pinfunction "10_10") (pintype "passive"))
      (node (ref "CPU2P") (pin "12") (pinfunction "12_12") (pintype "passive"))
      (node (ref "CPU2P") (pin "14") (pinfunction "14_14") (pintype "passive"))
      (node (ref "CPU2P") (pin "16") (pinfunction "16_16") (pintype "passive"))
      (node (ref "CPU2P") (pin "18") (pinfunction "18_18") (pintype "passive"))
      (node (ref "CPU2P") (pin "2") (pinfunction "2_2") (pintype "passive"))
      (node (ref "CPU2P") (pin "20") (pinfunction "20_20") (pintype "passive"))
      (node (ref "CPU2P") (pin "4") (pinfunction "4_4") (pintype "passive"))
      (node (ref "CPU2P") (pin "6") (pinfunction "6_6") (pintype "passive"))
      (node (ref "CPU2P") (pin "8") (pinfunction "8_8") (pintype "passive"))
      (node (ref "DAD1P") (pin "10") (pinfunction "10_10") (pintype "passive"))
      (node (ref "DAD1P") (pin "12") (pinfunction "12_12") (pintype "passive"))
      (node (ref "DAD1P") (pin "14") (pinfunction "14_14") (pintype "passive"))
      (node (ref "DAD1P") (pin "16") (pinfunction "16_16") (pintype "passive"))
      (node (ref "DAD1P") (pin "18") (pinfunction "18_18") (pintype "passive"))
      (node (ref "DAD1P") (pin "2") (pinfunction "2_2") (pintype "passive"))
      (node (ref "DAD1P") (pin "20") (pinfunction "20_20") (pintype "passive"))
      (node (ref "DAD1P") (pin "4") (pinfunction "4_4") (pintype "passive"))
      (node (ref "DAD1P") (pin "6") (pinfunction "6_6") (pintype "passive"))
      (node (ref "DAD1P") (pin "8") (pinfunction "8_8") (pintype "passive"))
      (node (ref "DAD2P") (pin "10") (pinfunction "10_10") (pintype "passive"))
      (node (ref "DAD2P") (pin "12") (pinfunction "12_12") (pintype "passive"))
      (node (ref "DAD2P") (pin "14") (pinfunction "14_14") (pintype "passive"))
      (node (ref "DAD2P") (pin "16") (pinfunction "16_16") (pintype "passive"))
      (node (ref "DAD2P") (pin "18") (pinfunction "18_18") (pintype "passive"))
      (node (ref "DAD2P") (pin "2") (pinfunction "2_2") (pintype "passive"))
      (node (ref "DAD2P") (pin "20") (pinfunction "20_20") (pintype "passive"))
      (node (ref "DAD2P") (pin "4") (pinfunction "4_4") (pintype "passive"))
      (node (ref "DAD2P") (pin "6") (pinfunction "6_6") (pintype "passive"))
      (node (ref "DAD2P") (pin "8") (pinfunction "8_8") (pintype "passive"))
      (node (ref "DAT1P") (pin "10") (pinfunction "10_10") (pintype "passive"))
      (node (ref "DAT1P") (pin "12") (pinfunction "12_12") (pintype "passive"))
      (node (ref "DAT1P") (pin "14") (pinfunction "14_14") (pintype "passive"))
      (node (ref "DAT1P") (pin "16") (pinfunction "16_16") (pintype "passive"))
      (node (ref "DAT1P") (pin "18") (pinfunction "18_18") (pintype "passive"))
      (node (ref "DAT1P") (pin "2") (pinfunction "2_2") (pintype "passive"))
      (node (ref "DAT1P") (pin "20") (pinfunction "20_20") (pintype "passive"))
      (node (ref "DAT1P") (pin "4") (pinfunction "4_4") (pintype "passive"))
      (node (ref "DAT1P") (pin "6") (pinfunction "6_6") (pintype "passive"))
      (node (ref "DAT1P") (pin "8") (pinfunction "8_8") (pintype "passive"))
      (node (ref "DAT2P") (pin "10") (pinfunction "10_10") (pintype "passive"))
      (node (ref "DAT2P") (pin "12") (pinfunction "12_12") (pintype "passive"))
      (node (ref "DAT2P") (pin "14") (pinfunction "14_14") (pintype "passive"))
      (node (ref "DAT2P") (pin "16") (pinfunction "16_16") (pintype "passive"))
      (node (ref "DAT2P") (pin "18") (pinfunction "18_18") (pintype "passive"))
      (node (ref "DAT2P") (pin "2") (pinfunction "2_2") (pintype "passive"))
      (node (ref "DAT2P") (pin "20") (pinfunction "20_20") (pintype "passive"))
      (node (ref "DAT2P") (pin "4") (pinfunction "4_4") (pintype "passive"))
      (node (ref "DAT2P") (pin "6") (pinfunction "6_6") (pintype "passive"))
      (node (ref "DAT2P") (pin "8") (pinfunction "8_8") (pintype "passive"))
      (node (ref "E3") (pin "14") (pinfunction "VSS_14") (pintype "power_in"))
      (node (ref "E3A") (pin "14") (pinfunction "VSS_14") (pintype "power_in"))
      (node (ref "E4") (pin "14") (pinfunction "VSS_14") (pintype "power_in"))
      (node (ref "E4A") (pin "14") (pinfunction "VSS_14") (pintype "power_in"))
      (node (ref "FIELDS") (pin "1") (pinfunction "1_1") (pintype "passive"))
      (node (ref "FIELDS") (pin "11") (pinfunction "11_11") (pintype "passive"))
      (node (ref "FIELDS") (pin "13") (pinfunction "13_13") (pintype "passive"))
      (node (ref "FIELDS") (pin "15") (pinfunction "15_15") (pintype "passive"))
      (node (ref "FIELDS") (pin "3") (pinfunction "3_3") (pintype "passive"))
      (node (ref "FIELDS") (pin "5") (pinfunction "5_5") (pintype "passive"))
      (node (ref "FIELDS") (pin "7") (pinfunction "7_7") (pintype "passive"))
      (node (ref "FIELDS") (pin "9") (pinfunction "9_9") (pintype "passive"))
      (node (ref "J2") (pin "A12") (pinfunction "GND_1_A12") (pintype "bidirectional"))
      (node (ref "J2") (pin "B12") (pinfunction "GND_2_B12") (pintype "bidirectional"))
      (node (ref "J2") (pin "S1") (pinfunction "SHELL_1_S1") (pintype "bidirectional"))
      (node (ref "J2") (pin "S2") (pinfunction "SHELL_2_S2") (pintype "bidirectional"))
      (node (ref "J2") (pin "S3") (pinfunction "SHELL_3_S3") (pintype "bidirectional"))
      (node (ref "J2") (pin "S4") (pinfunction "SHELL_4_S4") (pintype "bidirectional"))
      (node (ref "MEM1P") (pin "10") (pinfunction "10_10") (pintype "passive"))
      (node (ref "MEM1P") (pin "12") (pinfunction "12_12") (pintype "passive"))
      (node (ref "MEM1P") (pin "14") (pinfunction "14_14") (pintype "passive"))
      (node (ref "MEM1P") (pin "16") (pinfunction "16_16") (pintype "passive"))
      (node (ref "MEM1P") (pin "18") (pinfunction "18_18") (pintype "passive"))
      (node (ref "MEM1P") (pin "2") (pinfunction "2_2") (pintype "passive"))
      (node (ref "MEM1P") (pin "20") (pinfunction "20_20") (pintype "passive"))
      (node (ref "MEM1P") (pin "4") (pinfunction "4_4") (pintype "passive"))
      (node (ref "MEM1P") (pin "6") (pinfunction "6_6") (pintype "passive"))
      (node (ref "MEM1P") (pin "8") (pinfunction "8_8") (pintype "passive"))
      (node (ref "MEM2P") (pin "10") (pinfunction "10_10") (pintype "passive"))
      (node (ref "MEM2P") (pin "12") (pinfunction "12_12") (pintype "passive"))
      (node (ref "MEM2P") (pin "14") (pinfunction "14_14") (pintype "passive"))
      (node (ref "MEM2P") (pin "16") (pinfunction "16_16") (pintype "passive"))
      (node (ref "MEM2P") (pin "18") (pinfunction "18_18") (pintype "passive"))
      (node (ref "MEM2P") (pin "2") (pinfunction "2_2") (pintype "passive"))
      (node (ref "MEM2P") (pin "20") (pinfunction "20_20") (pintype "passive"))
      (node (ref "MEM2P") (pin "4") (pinfunction "4_4") (pintype "passive"))
      (node (ref "MEM2P") (pin "6") (pinfunction "6_6") (pintype "passive"))
      (node (ref "MEM2P") (pin "8") (pinfunction "8_8") (pintype "passive"))
      (node (ref "PANEL") (pin "10") (pinfunction "10_10") (pintype "passive"))
      (node (ref "PANEL") (pin "12") (pinfunction "12_12") (pintype "passive"))
      (node (ref "PANEL") (pin "14") (pinfunction "14_14") (pintype "passive"))
      (node (ref "PANEL") (pin "16") (pinfunction "16_16") (pintype "passive"))
      (node (ref "PANEL") (pin "18") (pinfunction "18_18") (pintype "passive"))
      (node (ref "PANEL") (pin "2") (pinfunction "2_2") (pintype "passive"))
      (node (ref "PANEL") (pin "20") (pinfunction "20_20") (pintype "passive"))
      (node (ref "PANEL") (pin "4") (pinfunction "4_4") (pintype "passive"))
      (node (ref "PANEL") (pin "6") (pinfunction "6_6") (pintype "passive"))
      (node (ref "PANEL") (pin "8") (pinfunction "8_8") (pintype "passive"))
      (node (ref "PROG1") (pin "10") (pinfunction "10_10") (pintype "passive"))
      (node (ref "PROG1") (pin "2") (pinfunction "2_2") (pintype "passive"))
      (node (ref "PROG2") (pin "10") (pinfunction "10_10") (pintype "passive"))
      (node (ref "PROG2") (pin "2") (pinfunction "2_2") (pintype "passive"))
      (node (ref "Q1") (pin "7") (pinfunction "GND_7") (pintype "power_in"))
      (node (ref "Q1A") (pin "4") (pinfunction "GND_4") (pintype "power_in"))
      (node (ref "R1") (pin "2") (pinfunction "2_2") (pintype "passive"))
      (node (ref "R10") (pin "2") (pinfunction "2_2") (pintype "passive"))
      (node (ref "R2") (pin "2") (pinfunction "2_2") (pintype "passive"))
      (node (ref "R3") (pin "2") (pinfunction "2_2") (pintype "passive"))
      (node (ref "R4") (pin "2") (pinfunction "2_2") (pintype "passive"))
      (node (ref "R5") (pin "2") (pinfunction "2_2") (pintype "passive"))
      (node (ref "R6") (pin "2") (pinfunction "2_2") (pintype "passive"))
      (node (ref "R7") (pin "2") (pinfunction "2_2") (pintype "passive"))
      (node (ref "R8") (pin "2") (pinfunction "2_2") (pintype "passive"))
      (node (ref "R9") (pin "2") (pinfunction "2_2") (pintype "passive"))
    )
    (net (code "52") (name "INIT") (class "Default")
      (node (ref "BAC2P") (pin "1") (pinfunction "1_1") (pintype "passive"))
      (node (ref "DAD2P") (pin "1") (pinfunction "1_1") (pintype "passive"))
      (node (ref "MMU8L") (pin "91") (pinfunction "IN/GCLR_91") (pintype "input"))
      (node (ref "R10") (pin "1") (pinfunction "1_1") (pintype "passive"))
    )
    (net (code "53") (name "IOP1") (class "Default")
      (node (ref "BAC2P") (pin "11") (pinfunction "11_11") (pintype "passive"))
      (node (ref "MMU8L") (pin "92") (pinfunction "IN/GCLK2/OE2_92") (pintype "input"))
      (node (ref "R5") (pin "1") (pinfunction "1_1") (pintype "passive"))
    )
    (net (code "54") (name "IOP2") (class "Default")
      (node (ref "BAC2P") (pin "9") (pinfunction "9_9") (pintype "passive"))
      (node (ref "MMU8L") (pin "87") (pinfunction "IO/GCLK3_87") (pintype "bidirectional"))
      (node (ref "R6") (pin "1") (pinfunction "1_1") (pintype "passive"))
    )
    (net (code "55") (name "IOP4") (class "Default")
      (node (ref "BAC2P") (pin "7") (pinfunction "7_7") (pintype "passive"))
      (node (ref "MMU8L") (pin "89") (pinfunction "IN/GCLK1_89") (pintype "input"))
      (node (ref "R7") (pin "1") (pinfunction "1_1") (pintype "passive"))
    )
    (net (code "56") (name "JMP_OR_JMS") (class "Default")
      (node (ref "CPU2P") (pin "15") (pinfunction "15_15") (pintype "passive"))
      (node (ref "MMU8L") (pin "18") (pinfunction "IO12_18") (pintype "bidirectional"))
    )
    (net (code "57") (name "MB00") (class "Default")
      (node (ref "BMB1P") (pin "17") (pinfunction "17_17") (pintype "passive"))
      (node (ref "MM32K") (pin "66") (pinfunction "IO51_66") (pintype "bidirectional"))
      (node (ref "MMU8L") (pin "49") (pinfunction "IO37_49") (pintype "bidirectional"))
    )
    (net (code "58") (name "MB01") (class "Default")
      (node (ref "BMB1P") (pin "15") (pinfunction "15_15") (pintype "passive"))
      (node (ref "MM32K") (pin "67") (pinfunction "IO52_67") (pintype "bidirectional"))
      (node (ref "MMU8L") (pin "50") (pinfunction "IO38_50") (pintype "bidirectional"))
    )
    (net (code "59") (name "MB02") (class "Default")
      (node (ref "BMB1P") (pin "13") (pinfunction "13_13") (pintype "passive"))
      (node (ref "MM32K") (pin "69") (pinfunction "IO53_69") (pintype "bidirectional"))
      (node (ref "MMU8L") (pin "51") (pinfunction "IO39_51") (pintype "bidirectional"))
    )
    (net (code "60") (name "MB03") (class "Default")
      (node (ref "BMB1P") (pin "9") (pinfunction "9_9") (pintype "passive"))
      (node (ref "MM32K") (pin "72") (pinfunction "IO56_72") (pintype "bidirectional"))
      (node (ref "MMU8L") (pin "56") (pinfunction "IO43_56") (pintype "bidirectional"))
    )
    (net (code "61") (name "MB04") (class "Default")
      (node (ref "BMB1P") (pin "5") (pinfunction "5_5") (pintype "passive"))
      (node (ref "MM32K") (pin "77") (pinfunction "IO59_77") (pintype "bidirectional"))
      (node (ref "MMU8L") (pin "59") (pinfunction "IO46_59") (pintype "bidirectional"))
    )
    (net (code "62") (name "MB05") (class "Default")
      (node (ref "BMB1P") (pin "1") (pinfunction "1_1") (pintype "passive"))
      (node (ref "MM32K") (pin "80") (pinfunction "IO62_80") (pintype "bidirectional"))
      (node (ref "MMU8L") (pin "63") (pinfunction "IO49_63") (pintype "bidirectional"))
    )
    (net (code "63") (name "MB06") (class "Default")
      (node (ref "BMB2P") (pin "15") (pinfunction "15_15") (pintype "passive"))
      (node (ref "MM32K") (pin "70") (pinfunction "IO54_70") (pintype "bidirectional"))
      (node (ref "MMU8L") (pin "52") (pinfunction "IO40_52") (pintype "bidirectional"))
    )
    (net (code "64") (name "MB07") (class "Default")
      (node (ref "BMB2P") (pin "11") (pinfunction "11_11") (pintype "passive"))
      (node (ref "MM32K") (pin "71") (pinfunction "IO55_71") (pintype "bidirectional"))
      (node (ref "MMU8L") (pin "55") (pinfunction "IO42_55") (pintype "bidirectional"))
    )
    (net (code "65") (name "MB08") (class "Default")
      (node (ref "BMB2P") (pin "7") (pinfunction "7_7") (pintype "passive"))
      (node (ref "MM32K") (pin "73") (pinfunction "IO57_73") (pintype "bidirectional"))
      (node (ref "MMU8L") (pin "57") (pinfunction "IO44_57") (pintype "bidirectional"))
    )
    (net (code "66") (name "MB09") (class "Default")
      (node (ref "BMB2P") (pin "5") (pinfunction "5_5") (pintype "passive"))
      (node (ref "MM32K") (pin "74") (pinfunction "IO58_74") (pintype "bidirectional"))
      (node (ref "MMU8L") (pin "58") (pinfunction "IO45_58") (pintype "bidirectional"))
    )
    (net (code "67") (name "MB10") (class "Default")
      (node (ref "BMB2P") (pin "3") (pinfunction "3_3") (pintype "passive"))
      (node (ref "MM32K") (pin "78") (pinfunction "IO60_78") (pintype "bidirectional"))
      (node (ref "MMU8L") (pin "60") (pinfunction "IO47_60") (pintype "bidirectional"))
    )
    (net (code "68") (name "MB11") (class "Default")
      (node (ref "BMB2P") (pin "1") (pinfunction "1_1") (pintype "passive"))
      (node (ref "MM32K") (pin "79") (pinfunction "IO61_79") (pintype "bidirectional"))
      (node (ref "MMU8L") (pin "62") (pinfunction "IO48_62") (pintype "bidirectional"))
    )
    (net (code "69") (name "MBODD_P") (class "Default")
      (node (ref "MEM2P") (pin "9") (pinfunction "9_9") (pintype "passive"))
      (node (ref "MM32K") (pin "11") (pinfunction "IO7_11") (pintype "bidirectional"))
    )
    (net (code "70") (name "MEM00") (class "Default")
      (node (ref "MEM1P") (pin "15") (pinfunction "15_15") (pintype "passive"))
      (node (ref "MM32K") (pin "21") (pinfunction "IO14_21") (pintype "bidirectional"))
    )
    (net (code "71") (name "MEM01") (class "Default")
      (node (ref "MEM1P") (pin "13") (pinfunction "13_13") (pintype "passive"))
      (node (ref "MM32K") (pin "18") (pinfunction "IO12_18") (pintype "bidirectional"))
    )
    (net (code "72") (name "MEM02") (class "Default")
      (node (ref "MEM1P") (pin "11") (pinfunction "11_11") (pintype "passive"))
      (node (ref "MM32K") (pin "15") (pinfunction "IO10_15") (pintype "bidirectional"))
    )
    (net (code "73") (name "MEM03") (class "Default")
      (node (ref "MEM1P") (pin "9") (pinfunction "9_9") (pintype "passive"))
      (node (ref "MM32K") (pin "12") (pinfunction "IO8_12") (pintype "bidirectional"))
    )
    (net (code "74") (name "MEM04") (class "Default")
      (node (ref "MEM1P") (pin "7") (pinfunction "7_7") (pintype "passive"))
      (node (ref "MM32K") (pin "10") (pinfunction "IO6_10") (pintype "bidirectional"))
    )
    (net (code "75") (name "MEM05") (class "Default")
      (node (ref "MEM1P") (pin "5") (pinfunction "5_5") (pintype "passive"))
      (node (ref "MM32K") (pin "9") (pinfunction "IO5_9") (pintype "bidirectional"))
    )
    (net (code "76") (name "MEM06") (class "Default")
      (node (ref "MEM1P") (pin "3") (pinfunction "3_3") (pintype "passive"))
      (node (ref "MM32K") (pin "8") (pinfunction "IO4_8") (pintype "bidirectional"))
    )
    (net (code "77") (name "MEM07") (class "Default")
      (node (ref "MEM1P") (pin "1") (pinfunction "1_1") (pintype "passive"))
      (node (ref "MM32K") (pin "4") (pinfunction "IO2_4") (pintype "bidirectional"))
    )
    (net (code "78") (name "MEM08") (class "Default")
      (node (ref "MEM2P") (pin "17") (pinfunction "17_17") (pintype "passive"))
      (node (ref "MM32K") (pin "22") (pinfunction "IO15_22") (pintype "bidirectional"))
    )
    (net (code "79") (name "MEM09") (class "Default")
      (node (ref "MEM2P") (pin "15") (pinfunction "15_15") (pintype "passive"))
      (node (ref "MM32K") (pin "19") (pinfunction "IO13_19") (pintype "bidirectional"))
    )
    (net (code "80") (name "MEM10") (class "Default")
      (node (ref "MEM2P") (pin "13") (pinfunction "13_13") (pintype "passive"))
      (node (ref "MM32K") (pin "16") (pinfunction "IO11_16") (pintype "bidirectional"))
    )
    (net (code "81") (name "MEM11") (class "Default")
      (node (ref "MEM2P") (pin "11") (pinfunction "11_11") (pintype "passive"))
      (node (ref "MM32K") (pin "14") (pinfunction "IO9_14") (pintype "bidirectional"))
    )
    (net (code "82") (name "MEMSTART") (class "Default")
      (node (ref "BMA2P") (pin "7") (pinfunction "7_7") (pintype "passive"))
      (node (ref "MM32K") (pin "96") (pinfunction "IO71_96") (pintype "bidirectional"))
      (node (ref "MMU8L") (pin "34") (pinfunction "IO26_34") (pintype "bidirectional"))
      (node (ref "R1") (pin "1") (pinfunction "1_1") (pintype "passive"))
    )
    (net (code "83") (name "MEM_P") (class "Default")
      (node (ref "MEM1P") (pin "17") (pinfunction "17_17") (pintype "passive"))
      (node (ref "MM32K") (pin "23") (pinfunction "IO16_23") (pintype "bidirectional"))
    )
    (net (code "84") (name "Net-(E3-I{slash}O5)") (class "Default")
      (node (ref "E3") (pin "17") (pinfunction "I/O5_17") (pintype "bidirectional"))
      (node (ref "E3A") (pin "17") (pinfunction "I/O5_17") (pintype "bidirectional"))
    )
    (net (code "85") (name "Net-(E3-I{slash}O6)") (class "Default")
      (node (ref "E3") (pin "18") (pinfunction "I/O6_18") (pintype "bidirectional"))
      (node (ref "E3A") (pin "18") (pinfunction "I/O6_18") (pintype "bidirectional"))
    )
    (net (code "86") (name "Net-(E3-I{slash}O7)") (class "Default")
      (node (ref "E3") (pin "19") (pinfunction "I/O7_19") (pintype "bidirectional"))
      (node (ref "E3A") (pin "19") (pinfunction "I/O7_19") (pintype "bidirectional"))
    )
    (net (code "87") (name "Net-(J2-CC1)") (class "Default")
      (node (ref "J2") (pin "A5") (pinfunction "CC1_A5") (pintype "bidirectional"))
      (node (ref "R3") (pin "1") (pinfunction "1_1") (pintype "passive"))
    )
    (net (code "88") (name "Net-(J2-CC2)") (class "Default")
      (node (ref "J2") (pin "B5") (pinfunction "CC2_B5") (pintype "bidirectional"))
      (node (ref "R4") (pin "1") (pinfunction "1_1") (pintype "passive"))
    )
    (net (code "89") (name "PARITY") (class "Default")
      (node (ref "E3") (pin "16") (pinfunction "I/O4_16") (pintype "bidirectional"))
      (node (ref "E3A") (pin "16") (pinfunction "I/O4_16") (pintype "bidirectional"))
      (node (ref "MM32K") (pin "33") (pinfunction "IO25_33") (pintype "bidirectional"))
    )
    (net (code "90") (name "POWER_OK") (class "Default")
      (node (ref "CPU2P") (pin "3") (pinfunction "3_3") (pintype "passive"))
      (node (ref "MMU8L") (pin "7") (pinfunction "IO3_7") (pintype "bidirectional"))
    )
    (net (code "91") (name "STOP_OK") (class "Default")
      (node (ref "CPU2P") (pin "5") (pinfunction "5_5") (pintype "passive"))
      (node (ref "MMU8L") (pin "9") (pinfunction "IO5_9") (pintype "bidirectional"))
    )
    (net (code "92") (name "TCK1") (class "Default")
      (node (ref "MMU8L") (pin "64") (pinfunction "TCK_64") (pintype "bidirectional"))
      (node (ref "PROG1") (pin "1") (pinfunction "1_1") (pintype "passive"))
    )
    (net (code "93") (name "TCK2") (class "Default")
      (node (ref "MM32K") (pin "64") (pinfunction "TCK_64") (pintype "bidirectional"))
      (node (ref "PROG2") (pin "1") (pinfunction "1_1") (pintype "passive"))
    )
    (net (code "94") (name "TDI1") (class "Default")
      (node (ref "MMU8L") (pin "6") (pinfunction "TDI_6") (pintype "bidirectional"))
      (node (ref "PROG1") (pin "9") (pinfunction "9_9") (pintype "passive"))
    )
    (net (code "95") (name "TDI2") (class "Default")
      (node (ref "MM32K") (pin "6") (pinfunction "TDI_6") (pintype "bidirectional"))
      (node (ref "PROG2") (pin "9") (pinfunction "9_9") (pintype "passive"))
    )
    (net (code "96") (name "TDO1") (class "Default")
      (node (ref "MMU8L") (pin "75") (pinfunction "TDO_75") (pintype "bidirectional"))
      (node (ref "PROG1") (pin "3") (pinfunction "3_3") (pintype "passive"))
    )
    (net (code "97") (name "TDO2") (class "Default")
      (node (ref "MM32K") (pin "75") (pinfunction "TDO_75") (pintype "bidirectional"))
      (node (ref "PROG2") (pin "3") (pinfunction "3_3") (pintype "passive"))
    )
    (net (code "98") (name "TMS1") (class "Default")
      (node (ref "MMU8L") (pin "17") (pinfunction "TMS_17") (pintype "bidirectional"))
      (node (ref "PROG1") (pin "5") (pinfunction "5_5") (pintype "passive"))
    )
    (net (code "99") (name "TMS2") (class "Default")
      (node (ref "MM32K") (pin "17") (pinfunction "TMS_17") (pintype "bidirectional"))
      (node (ref "PROG2") (pin "5") (pinfunction "5_5") (pintype "passive"))
    )
    (net (code "100") (name "TP2") (class "Default")
      (node (ref "BMA2P") (pin "3") (pinfunction "3_3") (pintype "passive"))
      (node (ref "MM32K") (pin "99") (pinfunction "IO73_99") (pintype "bidirectional"))
      (node (ref "MMU8L") (pin "32") (pinfunction "IO24_32") (pintype "bidirectional"))
      (node (ref "R2") (pin "1") (pinfunction "1_1") (pintype "passive"))
    )
    (net (code "101") (name "TP3") (class "Default")
      (node (ref "CPU1P") (pin "11") (pinfunction "11_11") (pintype "passive"))
      (node (ref "MMU8L") (pin "14") (pinfunction "IO9_14") (pintype "bidirectional"))
    )
    (net (code "102") (name "TS1") (class "Default")
      (node (ref "BAC2P") (pin "3") (pinfunction "3_3") (pintype "passive"))
      (node (ref "R9") (pin "1") (pinfunction "1_1") (pintype "passive"))
    )
    (net (code "103") (name "TS3") (class "Default")
      (node (ref "BAC2P") (pin "5") (pinfunction "5_5") (pintype "passive"))
      (node (ref "R8") (pin "1") (pinfunction "1_1") (pintype "passive"))
    )
    (net (code "104") (name "VCC") (class "Default")
      (node (ref "C1") (pin "1") (pinfunction "1_1") (pintype "passive"))
      (node (ref "C10") (pin "1") (pinfunction "1_1") (pintype "passive"))
      (node (ref "C11") (pin "1") (pinfunction "1_1") (pintype "passive"))
      (node (ref "C12") (pin "1") (pinfunction "1_1") (pintype "passive"))
      (node (ref "C13") (pin "1") (pinfunction "1_1") (pintype "passive"))
      (node (ref "C14") (pin "1") (pinfunction "1_1") (pintype "passive"))
      (node (ref "C15") (pin "1") (pinfunction "1_1") (pintype "passive"))
      (node (ref "C16") (pin "1") (pinfunction "1_1") (pintype "passive"))
      (node (ref "C17") (pin "1") (pinfunction "1_1") (pintype "passive"))
      (node (ref "C18") (pin "1") (pinfunction "1_1") (pintype "passive"))
      (node (ref "C19") (pin "1") (pinfunction "1_1") (pintype "passive"))
      (node (ref "C2") (pin "1") (pinfunction "1_1") (pintype "passive"))
      (node (ref "C20") (pin "1") (pinfunction "1_1") (pintype "passive"))
      (node (ref "C3") (pin "1") (pinfunction "1_1") (pintype "passive"))
      (node (ref "C4") (pin "1") (pinfunction "1_1") (pintype "passive"))
      (node (ref "C5") (pin "1") (pinfunction "1_1") (pintype "passive"))
      (node (ref "C6") (pin "1") (pinfunction "1_1") (pintype "passive"))
      (node (ref "C7") (pin "1") (pinfunction "1_1") (pintype "passive"))
      (node (ref "C8") (pin "1") (pinfunction "1_1") (pintype "passive"))
      (node (ref "C9") (pin "1") (pinfunction "1_1") (pintype "passive"))
      (node (ref "E3") (pin "28") (pinfunction "VCC_28") (pintype "power_in"))
      (node (ref "E3A") (pin "28") (pinfunction "VCC_28") (pintype "power_in"))
      (node (ref "E4") (pin "28") (pinfunction "VCC_28") (pintype "power_in"))
      (node (ref "E4A") (pin "28") (pinfunction "VCC_28") (pintype "power_in"))
      (node (ref "J2") (pin "A9") (pinfunction "VBUS_1_A9") (pintype "bidirectional"))
      (node (ref "J2") (pin "B9") (pinfunction "VBUS_2_B9") (pintype "bidirectional"))
      (node (ref "MM32K") (pin "20") (pinfunction "VCCIO_20") (pintype "power_in"))
      (node (ref "MM32K") (pin "36") (pinfunction "VCCIO_36") (pintype "power_in"))
      (node (ref "MM32K") (pin "41") (pinfunction "VCCINT_41") (pintype "power_in"))
      (node (ref "MM32K") (pin "5") (pinfunction "VCCIO_5") (pintype "power_in"))
      (node (ref "MM32K") (pin "53") (pinfunction "VCCIO_53") (pintype "power_in"))
      (node (ref "MM32K") (pin "68") (pinfunction "VCCIO_68") (pintype "power_in"))
      (node (ref "MM32K") (pin "84") (pinfunction "VCCIO_84") (pintype "power_in"))
      (node (ref "MM32K") (pin "93") (pinfunction "VCCINT_93") (pintype "power_in"))
      (node (ref "MMU8L") (pin "20") (pinfunction "VCCIO_20") (pintype "power_in"))
      (node (ref "MMU8L") (pin "36") (pinfunction "VCCIO_36") (pintype "power_in"))
      (node (ref "MMU8L") (pin "41") (pinfunction "VCCINT_41") (pintype "power_in"))
      (node (ref "MMU8L") (pin "5") (pinfunction "VCCIO_5") (pintype "power_in"))
      (node (ref "MMU8L") (pin "53") (pinfunction "VCCIO_53") (pintype "power_in"))
      (node (ref "MMU8L") (pin "68") (pinfunction "VCCIO_68") (pintype "power_in"))
      (node (ref "MMU8L") (pin "84") (pinfunction "VCCIO_84") (pintype "power_in"))
      (node (ref "MMU8L") (pin "93") (pinfunction "VCCINT_93") (pintype "power_in"))
      (node (ref "PROG1") (pin "4") (pinfunction "4_4") (pintype "passive"))
      (node (ref "PROG2") (pin "4") (pinfunction "4_4") (pintype "passive"))
      (node (ref "Q1") (pin "14") (pinfunction "VCC_14") (pintype "power_in"))
      (node (ref "Q1A") (pin "8") (pinfunction "VCC_8") (pintype "power_in"))
    )
    (net (code "105") (name "unconnected-(ACB1P-Pad19)") (class "Default")
      (node (ref "ACB1P") (pin "19") (pinfunction "19_19") (pintype "passive"))
    )
    (net (code "106") (name "unconnected-(ACB2P-Pad19)") (class "Default")
      (node (ref "ACB2P") (pin "19") (pinfunction "19_19") (pintype "passive"))
    )
    (net (code "107") (name "unconnected-(BAC1P-Pad19)") (class "Default")
      (node (ref "BAC1P") (pin "19") (pinfunction "19_19") (pintype "passive"))
    )
    (net (code "108") (name "unconnected-(BAC2P-Pad19)") (class "Default")
      (node (ref "BAC2P") (pin "19") (pinfunction "19_19") (pintype "passive"))
    )
    (net (code "109") (name "unconnected-(BMA1P-Pad19)") (class "Default")
      (node (ref "BMA1P") (pin "19") (pinfunction "19_19") (pintype "passive"))
    )
    (net (code "110") (name "unconnected-(BMA2P-Pad19)") (class "Default")
      (node (ref "BMA2P") (pin "19") (pinfunction "19_19") (pintype "passive"))
    )
    (net (code "111") (name "unconnected-(BMB1P-Pad19)") (class "Default")
      (node (ref "BMB1P") (pin "19") (pinfunction "19_19") (pintype "passive"))
    )
    (net (code "112") (name "unconnected-(BMB2P-Pad19)") (class "Default")
      (node (ref "BMB2P") (pin "19") (pinfunction "19_19") (pintype "passive"))
    )
    (net (code "113") (name "unconnected-(CPU1P-Pad19)") (class "Default")
      (node (ref "CPU1P") (pin "19") (pinfunction "19_19") (pintype "passive"))
    )
    (net (code "114") (name "unconnected-(CPU2P-Pad7)") (class "Default")
      (node (ref "CPU2P") (pin "7") (pinfunction "7_7") (pintype "passive"))
    )
    (net (code "115") (name "unconnected-(CPU2P-Pad9)") (class "Default")
      (node (ref "CPU2P") (pin "9") (pinfunction "9_9") (pintype "passive"))
    )
    (net (code "116") (name "unconnected-(CPU2P-Pad11)") (class "Default")
      (node (ref "CPU2P") (pin "11") (pinfunction "11_11") (pintype "passive"))
    )
    (net (code "117") (name "unconnected-(CPU2P-Pad19)") (class "Default")
      (node (ref "CPU2P") (pin "19") (pinfunction "19_19") (pintype "passive"))
    )
    (net (code "118") (name "unconnected-(DAD1P-Pad19)") (class "Default")
      (node (ref "DAD1P") (pin "19") (pinfunction "19_19") (pintype "passive"))
    )
    (net (code "119") (name "unconnected-(DAD2P-Pad19)") (class "Default")
      (node (ref "DAD2P") (pin "19") (pinfunction "19_19") (pintype "passive"))
    )
    (net (code "120") (name "unconnected-(DAT1P-Pad19)") (class "Default")
      (node (ref "DAT1P") (pin "19") (pinfunction "19_19") (pintype "passive"))
    )
    (net (code "121") (name "unconnected-(DAT2P-Pad19)") (class "Default")
      (node (ref "DAT2P") (pin "19") (pinfunction "19_19") (pintype "passive"))
    )
    (net (code "122") (name "unconnected-(MEM1P-Pad19)") (class "Default")
      (node (ref "MEM1P") (pin "19") (pinfunction "19_19") (pintype "passive"))
    )
    (net (code "123") (name "unconnected-(MEM2P-Pad5)") (class "Default")
      (node (ref "MEM2P") (pin "5") (pinfunction "5_5") (pintype "passive"))
    )
    (net (code "124") (name "unconnected-(MEM2P-Pad7)") (class "Default")
      (node (ref "MEM2P") (pin "7") (pinfunction "7_7") (pintype "passive"))
    )
    (net (code "125") (name "unconnected-(MEM2P-Pad19)") (class "Default")
      (node (ref "MEM2P") (pin "19") (pinfunction "19_19") (pintype "passive"))
    )
    (net (code "126") (name "unconnected-(MM32KQ-IN{slash}GCLK2{slash}OE2-Pad92)") (class "Default")
      (node (ref "MM32K") (pin "92") (pinfunction "IN/GCLK2/OE2_92") (pintype "input"))
    )
    (net (code "127") (name "unconnected-(MM32KQ-IN{slash}GCLR-Pad91)") (class "Default")
      (node (ref "MM32K") (pin "91") (pinfunction "IN/GCLR_91") (pintype "input"))
    )
    (net (code "128") (name "unconnected-(MM32KQ-IN{slash}OE1-Pad90)") (class "Default")
      (node (ref "MM32K") (pin "90") (pinfunction "IN/OE1_90") (pintype "input"))
    )
    (net (code "129") (name "unconnected-(MM32KQ-IO3-Pad7)") (class "Default")
      (node (ref "MM32K") (pin "7") (pinfunction "IO3_7") (pintype "bidirectional"))
    )
    (net (code "130") (name "unconnected-(MM32KQ-IO44-Pad57)") (class "Default")
      (node (ref "MM32K") (pin "57") (pinfunction "IO44_57") (pintype "bidirectional"))
    )
    (net (code "131") (name "unconnected-(MM32KQ-IO48-Pad62)") (class "Default")
      (node (ref "MM32K") (pin "62") (pinfunction "IO48_62") (pintype "bidirectional"))
    )
    (net (code "132") (name "unconnected-(MM32KQ-IO49-Pad63)") (class "Default")
      (node (ref "MM32K") (pin "63") (pinfunction "IO49_63") (pintype "bidirectional"))
    )
    (net (code "133") (name "unconnected-(MM32KQ-IO50-Pad65)") (class "Default")
      (node (ref "MM32K") (pin "65") (pinfunction "IO50_65") (pintype "bidirectional"))
    )
    (net (code "134") (name "unconnected-(MM32KQ-IO75-Pad1)") (class "Default")
      (node (ref "MM32K") (pin "1") (pinfunction "IO75_1") (pintype "bidirectional"))
    )
    (net (code "135") (name "unconnected-(MM32KQ-IO76-Pad2)") (class "Default")
      (node (ref "MM32K") (pin "2") (pinfunction "IO76_2") (pintype "bidirectional"))
    )
    (net (code "136") (name "unconnected-(MM32KQ-IO{slash}PD1-Pad3)") (class "Default")
      (node (ref "MM32K") (pin "3") (pinfunction "IO/PD1_3") (pintype "bidirectional"))
    )
    (net (code "137") (name "unconnected-(MMU8LQ-IN{slash}OE1-Pad90)") (class "Default")
      (node (ref "MMU8L") (pin "90") (pinfunction "IN/OE1_90") (pintype "input"))
    )
    (net (code "138") (name "unconnected-(MMU8LQ-IO28-Pad37)") (class "Default")
      (node (ref "MMU8L") (pin "37") (pinfunction "IO28_37") (pintype "bidirectional"))
    )
    (net (code "139") (name "unconnected-(MMU8LQ-IO41-Pad54)") (class "Default")
      (node (ref "MMU8L") (pin "54") (pinfunction "IO41_54") (pintype "bidirectional"))
    )
    (net (code "140") (name "unconnected-(MMU8LQ-IO69-Pad94)") (class "Default")
      (node (ref "MMU8L") (pin "94") (pinfunction "IO69_94") (pintype "bidirectional"))
    )
    (net (code "141") (name "unconnected-(MMU8LQ-IO72-Pad98)") (class "Default")
      (node (ref "MMU8L") (pin "98") (pinfunction "IO72_98") (pintype "bidirectional"))
    )
    (net (code "142") (name "unconnected-(MMU8LQ-IO75-Pad1)") (class "Default")
      (node (ref "MMU8L") (pin "1") (pinfunction "IO75_1") (pintype "bidirectional"))
    )
    (net (code "143") (name "unconnected-(MMU8LQ-IO76-Pad2)") (class "Default")
      (node (ref "MMU8L") (pin "2") (pinfunction "IO76_2") (pintype "bidirectional"))
    )
    (net (code "144") (name "unconnected-(PANEL-Pad19)") (class "Default")
      (node (ref "PANEL") (pin "19") (pinfunction "19_19") (pintype "passive"))
    )
    (net (code "145") (name "unconnected-(PROG1-Pad6)") (class "Default")
      (node (ref "PROG1") (pin "6") (pinfunction "6_6") (pintype "passive"))
    )
    (net (code "146") (name "unconnected-(PROG1-Pad7)") (class "Default")
      (node (ref "PROG1") (pin "7") (pinfunction "7_7") (pintype "passive"))
    )
    (net (code "147") (name "unconnected-(PROG1-Pad8)") (class "Default")
      (node (ref "PROG1") (pin "8") (pinfunction "8_8") (pintype "passive"))
    )
    (net (code "148") (name "unconnected-(PROG2-Pad6)") (class "Default")
      (node (ref "PROG2") (pin "6") (pinfunction "6_6") (pintype "passive"))
    )
    (net (code "149") (name "unconnected-(PROG2-Pad7)") (class "Default")
      (node (ref "PROG2") (pin "7") (pinfunction "7_7") (pintype "passive"))
    )
    (net (code "150") (name "unconnected-(PROG2-Pad8)") (class "Default")
      (node (ref "PROG2") (pin "8") (pinfunction "8_8") (pintype "passive"))
    )
    (net (code "151") (name "~{ACLR}") (class "Default")
      (node (ref "ACB2P") (pin "7") (pinfunction "7_7") (pintype "passive"))
      (node (ref "MMU8L") (pin "78") (pinfunction "IO60_78") (pintype "bidirectional"))
    )
    (net (code "152") (name "~{ADDA}") (class "Default")
      (node (ref "DAD2P") (pin "5") (pinfunction "5_5") (pintype "passive"))
    )
    (net (code "153") (name "~{BF_ENABLE}") (class "Default")
      (node (ref "CPU1P") (pin "13") (pinfunction "13_13") (pintype "passive"))
      (node (ref "MMU8L") (pin "16") (pinfunction "IO11_16") (pintype "bidirectional"))
    )
    (net (code "154") (name "~{BREAK}") (class "Default")
      (node (ref "DAD2P") (pin "7") (pinfunction "7_7") (pintype "passive"))
    )
    (net (code "155") (name "~{BRQ}") (class "Default")
      (node (ref "DAD2P") (pin "11") (pinfunction "11_11") (pintype "passive"))
    )
    (net (code "156") (name "~{CANCR}") (class "Default")
      (node (ref "DAT2P") (pin "9") (pinfunction "9_9") (pintype "passive"))
    )
    (net (code "157") (name "~{CS}") (class "Default")
      (node (ref "E3") (pin "20") (pinfunction "~{CS}_20") (pintype "input"))
      (node (ref "E3A") (pin "20") (pinfunction "~{CS}_20") (pintype "input"))
      (node (ref "E4") (pin "20") (pinfunction "~{CS}_20") (pintype "input"))
      (node (ref "E4A") (pin "20") (pinfunction "~{CS}_20") (pintype "input"))
      (node (ref "MM32K") (pin "52") (pinfunction "IO40_52") (pintype "bidirectional"))
    )
    (net (code "158") (name "~{CYC3}") (class "Default")
      (node (ref "DAT2P") (pin "11") (pinfunction "11_11") (pintype "passive"))
    )
    (net (code "159") (name "~{D-IN}") (class "Default")
      (node (ref "DAD2P") (pin "9") (pinfunction "9_9") (pintype "passive"))
    )
    (net (code "160") (name "~{DAD00}") (class "Default")
      (node (ref "DAD1P") (pin "17") (pinfunction "17_17") (pintype "passive"))
    )
    (net (code "161") (name "~{DAD01}") (class "Default")
      (node (ref "DAD1P") (pin "15") (pinfunction "15_15") (pintype "passive"))
    )
    (net (code "162") (name "~{DAD02}") (class "Default")
      (node (ref "DAD1P") (pin "13") (pinfunction "13_13") (pintype "passive"))
    )
    (net (code "163") (name "~{DAD03}") (class "Default")
      (node (ref "DAD1P") (pin "11") (pinfunction "11_11") (pintype "passive"))
    )
    (net (code "164") (name "~{DAD04}") (class "Default")
      (node (ref "DAD1P") (pin "9") (pinfunction "9_9") (pintype "passive"))
    )
    (net (code "165") (name "~{DAD05}") (class "Default")
      (node (ref "DAD1P") (pin "7") (pinfunction "7_7") (pintype "passive"))
    )
    (net (code "166") (name "~{DAD06}") (class "Default")
      (node (ref "DAD1P") (pin "5") (pinfunction "5_5") (pintype "passive"))
    )
    (net (code "167") (name "~{DAD07}") (class "Default")
      (node (ref "DAD1P") (pin "3") (pinfunction "3_3") (pintype "passive"))
    )
    (net (code "168") (name "~{DAD08}") (class "Default")
      (node (ref "DAD1P") (pin "1") (pinfunction "1_1") (pintype "passive"))
    )
    (net (code "169") (name "~{DAD09}") (class "Default")
      (node (ref "DAD2P") (pin "17") (pinfunction "17_17") (pintype "passive"))
    )
    (net (code "170") (name "~{DAD10}") (class "Default")
      (node (ref "DAD2P") (pin "15") (pinfunction "15_15") (pintype "passive"))
    )
    (net (code "171") (name "~{DAD11}") (class "Default")
      (node (ref "DAD2P") (pin "13") (pinfunction "13_13") (pintype "passive"))
    )
    (net (code "172") (name "~{DAT00}") (class "Default")
      (node (ref "DAT1P") (pin "17") (pinfunction "17_17") (pintype "passive"))
    )
    (net (code "173") (name "~{DAT01}") (class "Default")
      (node (ref "DAT1P") (pin "15") (pinfunction "15_15") (pintype "passive"))
    )
    (net (code "174") (name "~{DAT02}") (class "Default")
      (node (ref "DAT1P") (pin "13") (pinfunction "13_13") (pintype "passive"))
    )
    (net (code "175") (name "~{DAT03}") (class "Default")
      (node (ref "DAT1P") (pin "11") (pinfunction "11_11") (pintype "passive"))
    )
    (net (code "176") (name "~{DAT04}") (class "Default")
      (node (ref "DAT1P") (pin "9") (pinfunction "9_9") (pintype "passive"))
    )
    (net (code "177") (name "~{DAT05}") (class "Default")
      (node (ref "DAT1P") (pin "7") (pinfunction "7_7") (pintype "passive"))
    )
    (net (code "178") (name "~{DAT06}") (class "Default")
      (node (ref "DAT1P") (pin "5") (pinfunction "5_5") (pintype "passive"))
    )
    (net (code "179") (name "~{DAT07}") (class "Default")
      (node (ref "DAT1P") (pin "3") (pinfunction "3_3") (pintype "passive"))
    )
    (net (code "180") (name "~{DAT08}") (class "Default")
      (node (ref "DAT1P") (pin "1") (pinfunction "1_1") (pintype "passive"))
    )
    (net (code "181") (name "~{DAT09}") (class "Default")
      (node (ref "DAT2P") (pin "17") (pinfunction "17_17") (pintype "passive"))
    )
    (net (code "182") (name "~{DAT10}") (class "Default")
      (node (ref "DAT2P") (pin "15") (pinfunction "15_15") (pintype "passive"))
    )
    (net (code "183") (name "~{DAT11}") (class "Default")
      (node (ref "DAT2P") (pin "13") (pinfunction "13_13") (pintype "passive"))
    )
    (net (code "184") (name "~{DF_ENABLE}") (class "Default")
      (node (ref "CPU1P") (pin "17") (pinfunction "17_17") (pintype "passive"))
      (node (ref "MMU8L") (pin "22") (pinfunction "IO15_22") (pintype "bidirectional"))
    )
    (net (code "185") (name "~{EA0}") (class "Default")
      (node (ref "MM32K") (pin "58") (pinfunction "IO45_58") (pintype "bidirectional"))
      (node (ref "PANEL") (pin "5") (pinfunction "5_5") (pintype "passive"))
    )
    (net (code "186") (name "~{EA1}") (class "Default")
      (node (ref "MM32K") (pin "59") (pinfunction "IO46_59") (pintype "bidirectional"))
      (node (ref "PANEL") (pin "3") (pinfunction "3_3") (pintype "passive"))
    )
    (net (code "187") (name "~{EA2}") (class "Default")
      (node (ref "MM32K") (pin "60") (pinfunction "IO47_60") (pintype "bidirectional"))
      (node (ref "PANEL") (pin "1") (pinfunction "1_1") (pintype "passive"))
    )
    (net (code "188") (name "~{EA}") (class "Default")
      (node (ref "BMA1P") (pin "17") (pinfunction "17_17") (pintype "passive"))
      (node (ref "MMU8L") (pin "26") (pinfunction "IO19_26") (pintype "bidirectional"))
    )
    (net (code "189") (name "~{EMA}") (class "Default")
      (node (ref "MEM2P") (pin "1") (pinfunction "1_1") (pintype "passive"))
      (node (ref "MM32K") (pin "95") (pinfunction "IO70_95") (pintype "bidirectional"))
      (node (ref "MMU8L") (pin "38") (pinfunction "IO29_38") (pintype "bidirectional"))
    )
    (net (code "190") (name "~{EXDA0}") (class "Default")
      (node (ref "DAT2P") (pin "1") (pinfunction "1_1") (pintype "passive"))
      (node (ref "MMU8L") (pin "23") (pinfunction "IO16_23") (pintype "bidirectional"))
    )
    (net (code "191") (name "~{EXDA1}") (class "Default")
      (node (ref "DAT2P") (pin "3") (pinfunction "3_3") (pintype "passive"))
      (node (ref "MMU8L") (pin "24") (pinfunction "IO17_24") (pintype "bidirectional"))
    )
    (net (code "192") (name "~{EXDA2}") (class "Default")
      (node (ref "DAT2P") (pin "5") (pinfunction "5_5") (pintype "passive"))
      (node (ref "MMU8L") (pin "25") (pinfunction "IO18_25") (pintype "bidirectional"))
    )
    (net (code "193") (name "~{FS0}") (class "Default")
      (node (ref "FIELDS") (pin "16") (pinfunction "16_16") (pintype "passive"))
      (node (ref "MM32K") (pin "32") (pinfunction "IO24_32") (pintype "bidirectional"))
    )
    (net (code "194") (name "~{FS1}") (class "Default")
      (node (ref "FIELDS") (pin "14") (pinfunction "14_14") (pintype "passive"))
      (node (ref "MM32K") (pin "31") (pinfunction "IO23_31") (pintype "bidirectional"))
    )
    (net (code "195") (name "~{FS2}") (class "Default")
      (node (ref "FIELDS") (pin "12") (pinfunction "12_12") (pintype "passive"))
      (node (ref "MM32K") (pin "30") (pinfunction "IO22_30") (pintype "bidirectional"))
    )
    (net (code "196") (name "~{FS3}") (class "Default")
      (node (ref "FIELDS") (pin "10") (pinfunction "10_10") (pintype "passive"))
      (node (ref "MM32K") (pin "29") (pinfunction "IO21_29") (pintype "bidirectional"))
    )
    (net (code "197") (name "~{FS4}") (class "Default")
      (node (ref "FIELDS") (pin "8") (pinfunction "8_8") (pintype "passive"))
      (node (ref "MM32K") (pin "27") (pinfunction "IO20_27") (pintype "bidirectional"))
    )
    (net (code "198") (name "~{FS5}") (class "Default")
      (node (ref "FIELDS") (pin "6") (pinfunction "6_6") (pintype "passive"))
      (node (ref "MM32K") (pin "26") (pinfunction "IO19_26") (pintype "bidirectional"))
    )
    (net (code "199") (name "~{FS6}") (class "Default")
      (node (ref "FIELDS") (pin "4") (pinfunction "4_4") (pintype "passive"))
      (node (ref "MM32K") (pin "25") (pinfunction "IO18_25") (pintype "bidirectional"))
    )
    (net (code "200") (name "~{FS7}") (class "Default")
      (node (ref "FIELDS") (pin "2") (pinfunction "2_2") (pintype "passive"))
      (node (ref "MM32K") (pin "24") (pinfunction "IO17_24") (pintype "bidirectional"))
    )
    (net (code "201") (name "~{IB00}") (class "Default")
      (node (ref "ACB1P") (pin "17") (pinfunction "17_17") (pintype "passive"))
      (node (ref "MMU8L") (pin "66") (pinfunction "IO51_66") (pintype "bidirectional"))
    )
    (net (code "202") (name "~{IB01}") (class "Default")
      (node (ref "ACB1P") (pin "15") (pinfunction "15_15") (pintype "passive"))
      (node (ref "MMU8L") (pin "69") (pinfunction "IO53_69") (pintype "bidirectional"))
    )
    (net (code "203") (name "~{IB02}") (class "Default")
      (node (ref "ACB1P") (pin "13") (pinfunction "13_13") (pintype "passive"))
      (node (ref "MMU8L") (pin "71") (pinfunction "IO55_71") (pintype "bidirectional"))
    )
    (net (code "204") (name "~{IB03}") (class "Default")
      (node (ref "ACB1P") (pin "11") (pinfunction "11_11") (pintype "passive"))
      (node (ref "MMU8L") (pin "73") (pinfunction "IO57_73") (pintype "bidirectional"))
    )
    (net (code "205") (name "~{IB04}") (class "Default")
      (node (ref "ACB1P") (pin "9") (pinfunction "9_9") (pintype "passive"))
      (node (ref "MMU8L") (pin "77") (pinfunction "IO59_77") (pintype "bidirectional"))
    )
    (net (code "206") (name "~{IB05}") (class "Default")
      (node (ref "ACB1P") (pin "7") (pinfunction "7_7") (pintype "passive"))
      (node (ref "MMU8L") (pin "79") (pinfunction "IO61_79") (pintype "bidirectional"))
    )
    (net (code "207") (name "~{IB06}") (class "Default")
      (node (ref "ACB1P") (pin "5") (pinfunction "5_5") (pintype "passive"))
      (node (ref "MMU8L") (pin "81") (pinfunction "IO63_81") (pintype "bidirectional"))
    )
    (net (code "208") (name "~{IB07}") (class "Default")
      (node (ref "ACB1P") (pin "3") (pinfunction "3_3") (pintype "passive"))
      (node (ref "MMU8L") (pin "83") (pinfunction "IO65_83") (pintype "bidirectional"))
    )
    (net (code "209") (name "~{IB08}") (class "Default")
      (node (ref "ACB1P") (pin "1") (pinfunction "1_1") (pintype "passive"))
      (node (ref "MMU8L") (pin "86") (pinfunction "IO67_86") (pintype "bidirectional"))
    )
    (net (code "210") (name "~{IB09}") (class "Default")
      (node (ref "ACB2P") (pin "17") (pinfunction "17_17") (pintype "passive"))
      (node (ref "MMU8L") (pin "65") (pinfunction "IO50_65") (pintype "bidirectional"))
    )
    (net (code "211") (name "~{IB10}") (class "Default")
      (node (ref "ACB2P") (pin "15") (pinfunction "15_15") (pintype "passive"))
      (node (ref "MMU8L") (pin "67") (pinfunction "IO52_67") (pintype "bidirectional"))
    )
    (net (code "212") (name "~{IB11}") (class "Default")
      (node (ref "ACB2P") (pin "13") (pinfunction "13_13") (pintype "passive"))
      (node (ref "MMU8L") (pin "70") (pinfunction "IO54_70") (pintype "bidirectional"))
    )
    (net (code "213") (name "~{INT_INH}") (class "Default")
      (node (ref "CPU1P") (pin "7") (pinfunction "7_7") (pintype "passive"))
      (node (ref "MMU8L") (pin "11") (pinfunction "IO7_11") (pintype "bidirectional"))
    )
    (net (code "214") (name "~{IRQ}") (class "Default")
      (node (ref "ACB2P") (pin "9") (pinfunction "9_9") (pintype "passive"))
      (node (ref "MMU8L") (pin "74") (pinfunction "IO58_74") (pintype "bidirectional"))
    )
    (net (code "215") (name "~{KEY_CLR}") (class "Default")
      (node (ref "CPU1P") (pin "9") (pinfunction "9_9") (pintype "passive"))
      (node (ref "MMU8L") (pin "12") (pinfunction "IO8_12") (pintype "bidirectional"))
    )
    (net (code "216") (name "~{KEY_DF0}") (class "Default")
      (node (ref "MMU8L") (pin "100") (pinfunction "IO74_100") (pintype "bidirectional"))
      (node (ref "PANEL") (pin "11") (pinfunction "11_11") (pintype "passive"))
    )
    (net (code "217") (name "~{KEY_DF1}") (class "Default")
      (node (ref "MMU8L") (pin "99") (pinfunction "IO73_99") (pintype "bidirectional"))
      (node (ref "PANEL") (pin "9") (pinfunction "9_9") (pintype "passive"))
    )
    (net (code "218") (name "~{KEY_DF2}") (class "Default")
      (node (ref "CPU1P") (pin "1") (pinfunction "1_1") (pintype "passive"))
      (node (ref "MMU8L") (pin "4") (pinfunction "IO2_4") (pintype "bidirectional"))
      (node (ref "PANEL") (pin "7") (pinfunction "7_7") (pintype "passive"))
    )
    (net (code "219") (name "~{KEY_IF0}") (class "Default")
      (node (ref "MMU8L") (pin "95") (pinfunction "IO70_95") (pintype "bidirectional"))
      (node (ref "PANEL") (pin "17") (pinfunction "17_17") (pintype "passive"))
    )
    (net (code "220") (name "~{KEY_IF1}") (class "Default")
      (node (ref "MMU8L") (pin "96") (pinfunction "IO71_96") (pintype "bidirectional"))
      (node (ref "PANEL") (pin "15") (pinfunction "15_15") (pintype "passive"))
    )
    (net (code "221") (name "~{KEY_IF2}") (class "Default")
      (node (ref "CPU1P") (pin "3") (pinfunction "3_3") (pintype "passive"))
      (node (ref "MMU8L") (pin "8") (pinfunction "IO4_8") (pintype "bidirectional"))
      (node (ref "PANEL") (pin "13") (pinfunction "13_13") (pintype "passive"))
    )
    (net (code "222") (name "~{KEY_LOAD}") (class "Default")
      (node (ref "CPU2P") (pin "13") (pinfunction "13_13") (pintype "passive"))
      (node (ref "MMU8L") (pin "15") (pinfunction "IO10_15") (pintype "bidirectional"))
    )
    (net (code "223") (name "~{LINE}") (class "Default")
      (node (ref "ACB2P") (pin "1") (pinfunction "1_1") (pintype "passive"))
      (node (ref "MMU8L") (pin "85") (pinfunction "IO66_85") (pintype "bidirectional"))
    )
    (net (code "224") (name "~{LOAD_SF}") (class "Default")
      (node (ref "CPU1P") (pin "5") (pinfunction "5_5") (pintype "passive"))
      (node (ref "MMU8L") (pin "10") (pinfunction "IO6_10") (pintype "bidirectional"))
    )
    (net (code "225") (name "~{MB03}") (class "Default")
      (node (ref "BMB1P") (pin "11") (pinfunction "11_11") (pintype "passive"))
    )
    (net (code "226") (name "~{MB04}") (class "Default")
      (node (ref "BMB1P") (pin "7") (pinfunction "7_7") (pintype "passive"))
    )
    (net (code "227") (name "~{MB05}") (class "Default")
      (node (ref "BMB1P") (pin "3") (pinfunction "3_3") (pintype "passive"))
    )
    (net (code "228") (name "~{MB06}") (class "Default")
      (node (ref "BMB2P") (pin "17") (pinfunction "17_17") (pintype "passive"))
    )
    (net (code "229") (name "~{MB07}") (class "Default")
      (node (ref "BMB2P") (pin "13") (pinfunction "13_13") (pintype "passive"))
    )
    (net (code "230") (name "~{MB08}") (class "Default")
      (node (ref "BMB2P") (pin "9") (pinfunction "9_9") (pintype "passive"))
    )
    (net (code "231") (name "~{MEMDONE}") (class "Default")
      (node (ref "BMA2P") (pin "1") (pinfunction "1_1") (pintype "passive"))
      (node (ref "MM32K") (pin "100") (pinfunction "IO74_100") (pintype "bidirectional"))
      (node (ref "MMU8L") (pin "31") (pinfunction "IO23_31") (pintype "bidirectional"))
    )
    (net (code "232") (name "~{MNCR}") (class "Default")
      (node (ref "DAD2P") (pin "3") (pinfunction "3_3") (pintype "passive"))
    )
    (net (code "233") (name "~{OE}") (class "Default")
      (node (ref "E3") (pin "22") (pinfunction "~{OE}_22") (pintype "input"))
      (node (ref "E3A") (pin "22") (pinfunction "~{OE}_22") (pintype "input"))
      (node (ref "E4") (pin "22") (pinfunction "~{OE}_22") (pintype "input"))
      (node (ref "E4A") (pin "22") (pinfunction "~{OE}_22") (pintype "input"))
      (node (ref "MM32K") (pin "51") (pinfunction "IO39_51") (pintype "bidirectional"))
    )
    (net (code "234") (name "~{RUN}") (class "Default")
      (node (ref "ACB2P") (pin "5") (pinfunction "5_5") (pintype "passive"))
      (node (ref "MMU8L") (pin "80") (pinfunction "IO62_80") (pintype "bidirectional"))
    )
    (net (code "235") (name "~{SKIP}") (class "Default")
      (node (ref "ACB2P") (pin "11") (pinfunction "11_11") (pintype "passive"))
      (node (ref "MMU8L") (pin "72") (pinfunction "IO56_72") (pintype "bidirectional"))
    )
    (net (code "236") (name "~{SP_CYC_NEXT}") (class "Default")
      (node (ref "CPU1P") (pin "15") (pinfunction "15_15") (pintype "passive"))
      (node (ref "MMU8L") (pin "19") (pinfunction "IO13_19") (pintype "bidirectional"))
    )
    (net (code "237") (name "~{STROBE}") (class "Default")
      (node (ref "BMA2P") (pin "5") (pinfunction "5_5") (pintype "passive"))
      (node (ref "MM32K") (pin "98") (pinfunction "IO72_98") (pintype "bidirectional"))
      (node (ref "MMU8L") (pin "33") (pinfunction "IO25_33") (pintype "bidirectional"))
    )
    (net (code "238") (name "~{TTINST}") (class "Default")
      (node (ref "ACB2P") (pin "3") (pinfunction "3_3") (pintype "passive"))
      (node (ref "MMU8L") (pin "82") (pinfunction "IO64_82") (pintype "bidirectional"))
    )
    (net (code "239") (name "~{WCOVF}") (class "Default")
      (node (ref "DAT2P") (pin "7") (pinfunction "7_7") (pintype "passive"))
    )
    (net (code "240") (name "~{WE}") (class "Default")
      (node (ref "E3") (pin "27") (pinfunction "~{WE}_27") (pintype "input"))
      (node (ref "E3A") (pin "27") (pinfunction "~{WE}_27") (pintype "input"))
      (node (ref "E4") (pin "27") (pinfunction "~{WE}_27") (pintype "input"))
      (node (ref "E4A") (pin "27") (pinfunction "~{WE}_27") (pintype "input"))
      (node (ref "MM32K") (pin "50") (pinfunction "IO38_50") (pintype "bidirectional"))
    )
  )
)
